# STM32-E407_Rev_E.net
KiCad netlist of a schematic drawn in EAGLE
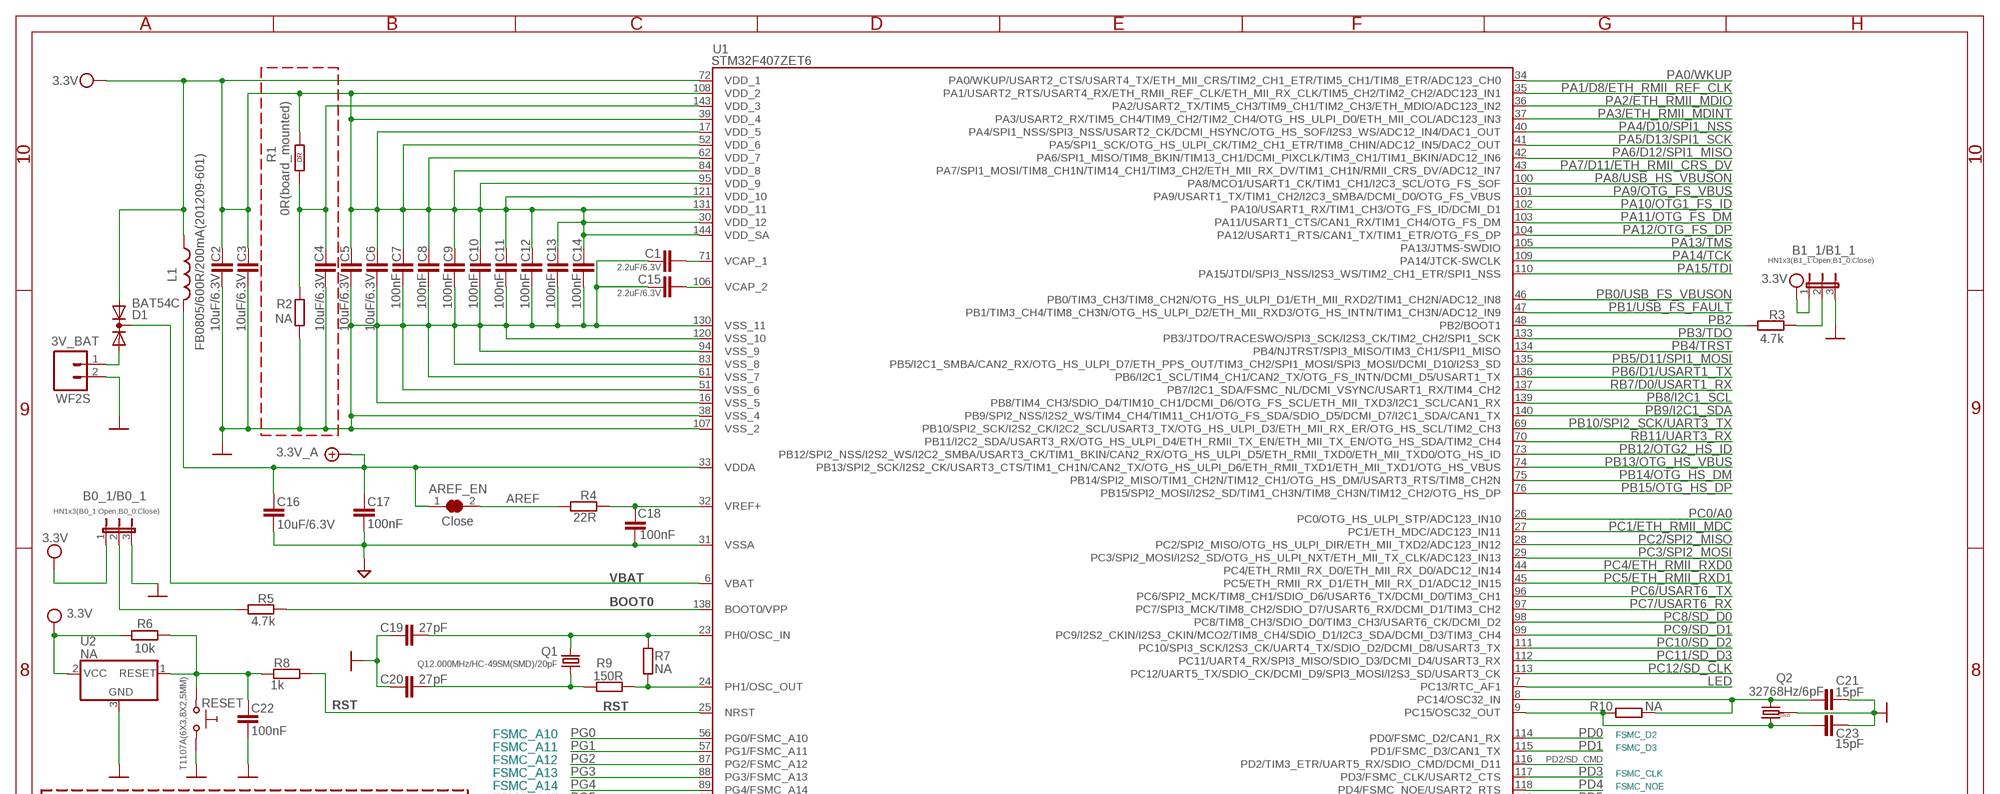
[diagram p0: schematic, sheet 1, part 1 of 2]
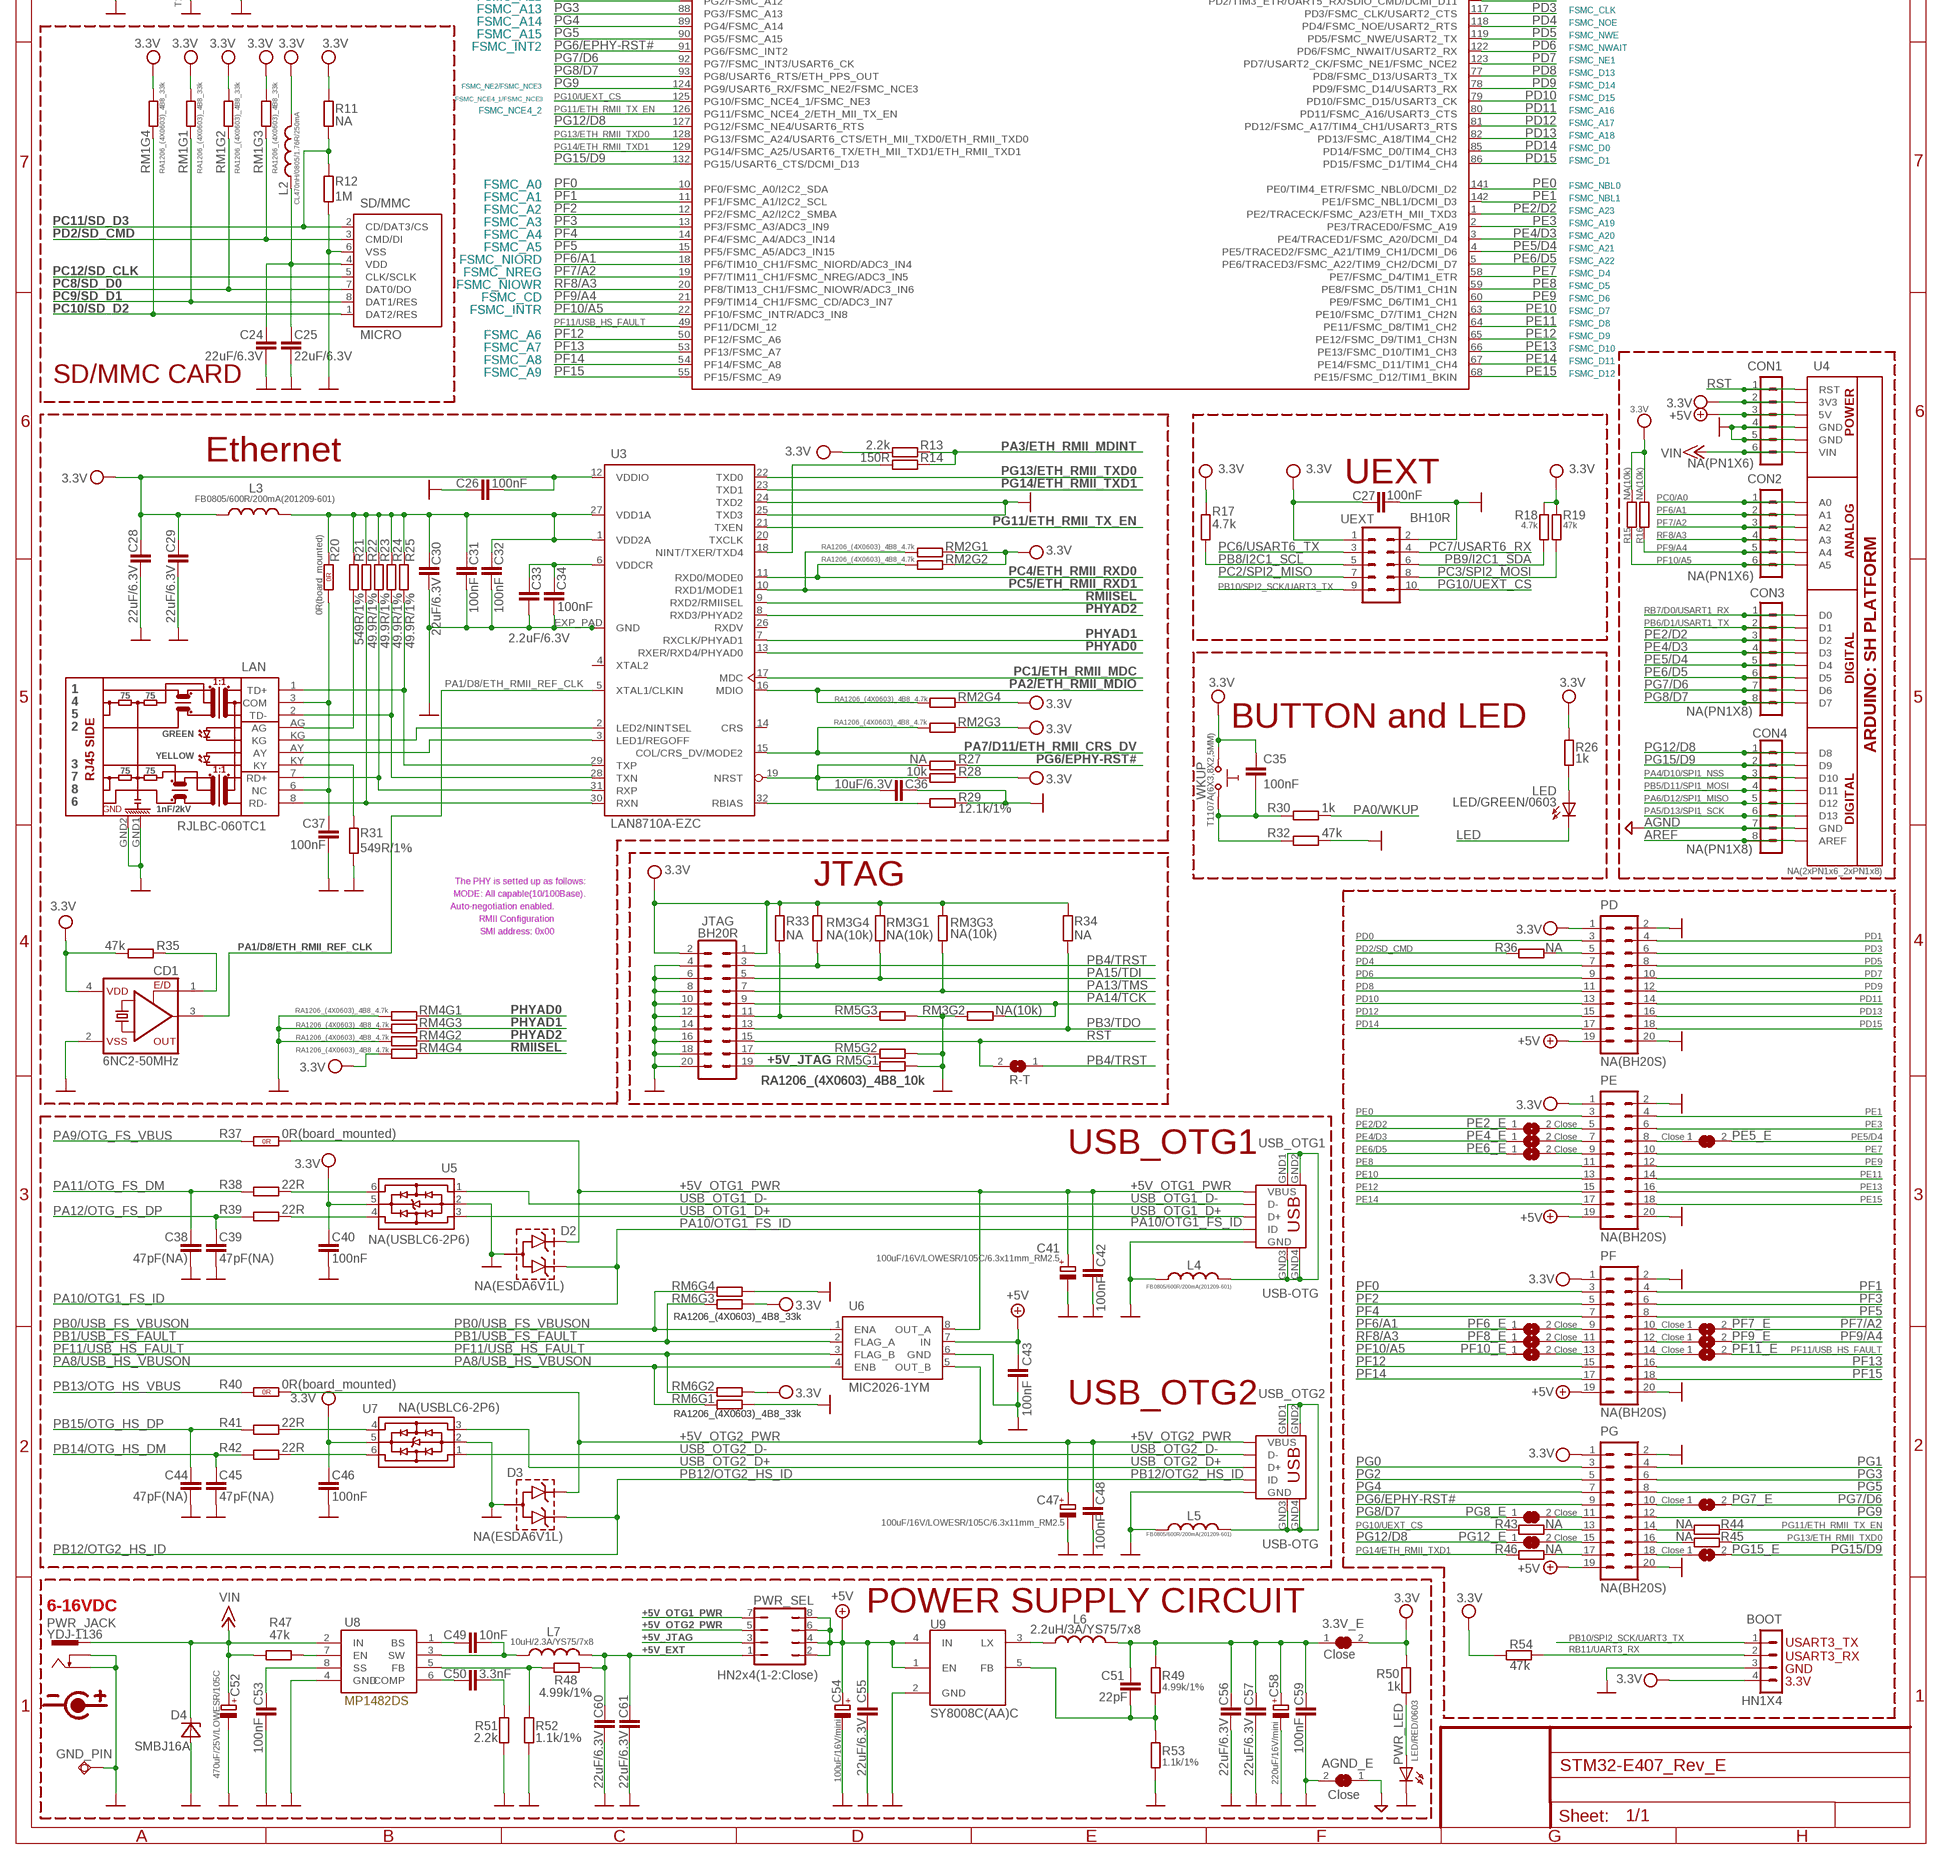
[diagram p1: schematic, sheet 1, part 2 of 2]

(export (version "E")
  (design (tool "Eeschema 10.0.6"))
  (components
    (comp (ref "3.3V_E")
      (value "Close")
      (footprint "eagle-import:SJ_1_SMALLER_CLOSE")
      (libsource (lib "eagle-import") (part "SJSJ_1_SMALLER_CLOSE"))
    )
    (comp (ref "3V_BAT")
      (value "WF2S")
      (footprint "eagle-import:CON2.54MM-2-0")
      (libsource (lib "eagle-import") (part "CON2PV2-2.54MM"))
    )
    (comp (ref "AGND_E")
      (value "Close")
      (footprint "eagle-import:SJ_1_SMALLER_CLOSE")
      (libsource (lib "eagle-import") (part "SJSJ_1_SMALLER_CLOSE"))
    )
    (comp (ref "AREF_EN")
      (value "Close")
      (footprint "eagle-import:SJ_1_SMALLER_CLOSE")
      (libsource (lib "eagle-import") (part "SJSJ_1_SMALLER_CLOSE"))
    )
    (comp (ref "B0_1/B0_1")
      (value "HN1x3(B0_1:Open;B0_0:Close)")
      (footprint "eagle-import:JP2")
      (libsource (lib "eagle-import") (part "JP2E"))
    )
    (comp (ref "B1_1/B1_1")
      (value "HN1x3(B1_1:Open;B1_0:Close)")
      (footprint "eagle-import:JP2")
      (libsource (lib "eagle-import") (part "JP2E"))
    )
    (comp (ref "BOOT")
      (value "HN1X4")
      (footprint "eagle-import:HN1X4")
      (libsource (lib "eagle-import") (part "CON4HN1X4"))
    )
    (comp (ref "C1")
      (value "2.2uF/6.3V")
      (footprint "eagle-import:C0603_DWS")
      (libsource (lib "eagle-import") (part "C-EUC0603_DWS"))
    )
    (comp (ref "C2")
      (value "10uF/6.3V")
      (footprint "eagle-import:C0603_DWS")
      (libsource (lib "eagle-import") (part "C-EUC0603_DWS"))
    )
    (comp (ref "C3")
      (value "10uF/6.3V")
      (footprint "eagle-import:C0603_DWS")
      (libsource (lib "eagle-import") (part "C-EUC0603_DWS"))
    )
    (comp (ref "C4")
      (value "10uF/6.3V")
      (footprint "eagle-import:C0603_DWS")
      (libsource (lib "eagle-import") (part "C-EUC0603_DWS"))
    )
    (comp (ref "C5")
      (value "10uF/6.3V")
      (footprint "eagle-import:C0603_DWS")
      (libsource (lib "eagle-import") (part "C-EUC0603_DWS"))
    )
    (comp (ref "C6")
      (value "10uF/6.3V")
      (footprint "eagle-import:C0603_DWS")
      (libsource (lib "eagle-import") (part "C-EUC0603_DWS"))
    )
    (comp (ref "C7")
      (value "100nF")
      (footprint "eagle-import:C0603_DWS")
      (libsource (lib "eagle-import") (part "C-EUC0603_DWS"))
    )
    (comp (ref "C8")
      (value "100nF")
      (footprint "eagle-import:C0603_DWS")
      (libsource (lib "eagle-import") (part "C-EUC0603_DWS"))
    )
    (comp (ref "C9")
      (value "100nF")
      (footprint "eagle-import:C0603_DWS")
      (libsource (lib "eagle-import") (part "C-EUC0603_DWS"))
    )
    (comp (ref "C10")
      (value "100nF")
      (footprint "eagle-import:C0603_DWS")
      (libsource (lib "eagle-import") (part "C-EUC0603_DWS"))
    )
    (comp (ref "C11")
      (value "100nF")
      (footprint "eagle-import:C0603_DWS")
      (libsource (lib "eagle-import") (part "C-EUC0603_DWS"))
    )
    (comp (ref "C12")
      (value "100nF")
      (footprint "eagle-import:C0603_DWS")
      (libsource (lib "eagle-import") (part "C-EUC0603_DWS"))
    )
    (comp (ref "C13")
      (value "100nF")
      (footprint "eagle-import:C0603_DWS")
      (libsource (lib "eagle-import") (part "C-EUC0603_DWS"))
    )
    (comp (ref "C14")
      (value "100nF")
      (footprint "eagle-import:C0603_DWS")
      (libsource (lib "eagle-import") (part "C-EUC0603_DWS"))
    )
    (comp (ref "C15")
      (value "2.2uF/6.3V")
      (footprint "eagle-import:C0603_DWS")
      (libsource (lib "eagle-import") (part "C-EUC0603_DWS"))
    )
    (comp (ref "C16")
      (value "10uF/6.3V")
      (footprint "eagle-import:C0603_DWS")
      (libsource (lib "eagle-import") (part "C-EUC0603_DWS"))
    )
    (comp (ref "C17")
      (value "100nF")
      (footprint "eagle-import:C0603_DWS")
      (libsource (lib "eagle-import") (part "C-EUC0603_DWS"))
    )
    (comp (ref "C18")
      (value "100nF")
      (footprint "eagle-import:C0603_DWS")
      (libsource (lib "eagle-import") (part "C-EUC0603_DWS"))
    )
    (comp (ref "C19")
      (value "27pF")
      (footprint "eagle-import:C0603_DWS")
      (libsource (lib "eagle-import") (part "C-EUC0603_DWS"))
    )
    (comp (ref "C20")
      (value "27pF")
      (footprint "eagle-import:C0603_DWS")
      (libsource (lib "eagle-import") (part "C-EUC0603_DWS"))
    )
    (comp (ref "C21")
      (value "15pF")
      (footprint "eagle-import:C0603_DWS")
      (libsource (lib "eagle-import") (part "C-EUC0603_DWS"))
    )
    (comp (ref "C22")
      (value "100nF")
      (footprint "eagle-import:C0603_DWS")
      (libsource (lib "eagle-import") (part "C-EUC0603_DWS"))
    )
    (comp (ref "C23")
      (value "15pF")
      (footprint "eagle-import:C0603_DWS")
      (libsource (lib "eagle-import") (part "C-EUC0603_DWS"))
    )
    (comp (ref "C24")
      (value "22uF/6.3V")
      (footprint "eagle-import:C0603_DWS")
      (libsource (lib "eagle-import") (part "C-EUC0603_DWS"))
    )
    (comp (ref "C25")
      (value "22uF/6.3V")
      (footprint "eagle-import:C0603_DWS")
      (libsource (lib "eagle-import") (part "C-EUC0603_DWS"))
    )
    (comp (ref "C26")
      (value "100nF")
      (footprint "eagle-import:C0603_DWS")
      (libsource (lib "eagle-import") (part "C-EUC0603_DWS"))
    )
    (comp (ref "C27")
      (value "100nF")
      (footprint "eagle-import:C0603_DWS")
      (libsource (lib "eagle-import") (part "C-EUC0603_DWS"))
    )
    (comp (ref "C28")
      (value "22uF/6.3V")
      (footprint "eagle-import:C0603_DWS")
      (libsource (lib "eagle-import") (part "C-EUC0603_DWS"))
    )
    (comp (ref "C29")
      (value "22uF/6.3V")
      (footprint "eagle-import:C0603_DWS")
      (libsource (lib "eagle-import") (part "C-EUC0603_DWS"))
    )
    (comp (ref "C30")
      (value "22uF/6.3V")
      (footprint "eagle-import:C0603_DWS")
      (libsource (lib "eagle-import") (part "C-EUC0603_DWS"))
    )
    (comp (ref "C31")
      (value "100nF")
      (footprint "eagle-import:C0603_DWS")
      (libsource (lib "eagle-import") (part "C-EUC0603_DWS"))
    )
    (comp (ref "C32")
      (value "100nF")
      (footprint "eagle-import:C0603_DWS")
      (libsource (lib "eagle-import") (part "C-EUC0603_DWS"))
    )
    (comp (ref "C33")
      (value "2.2uF/6.3V")
      (footprint "eagle-import:C0603_DWS")
      (libsource (lib "eagle-import") (part "C-EUC0603_DWS"))
    )
    (comp (ref "C34")
      (value "100nF")
      (footprint "eagle-import:C0603_DWS")
      (libsource (lib "eagle-import") (part "C-EUC0603_DWS"))
    )
    (comp (ref "C35")
      (value "100nF")
      (footprint "eagle-import:C0603_DWS")
      (libsource (lib "eagle-import") (part "C-EUC0603_DWS"))
    )
    (comp (ref "C36")
      (value "10uF/6.3V")
      (footprint "eagle-import:C0603_DWS")
      (libsource (lib "eagle-import") (part "C-EUC0603_DWS"))
    )
    (comp (ref "C37")
      (value "100nF")
      (footprint "eagle-import:C0603_DWS")
      (libsource (lib "eagle-import") (part "C-EUC0603_DWS"))
    )
    (comp (ref "C38")
      (value "47pF(NA)")
      (footprint "eagle-import:C0603_DWS")
      (libsource (lib "eagle-import") (part "C-EUC0603_DWS"))
    )
    (comp (ref "C39")
      (value "47pF(NA)")
      (footprint "eagle-import:C0603_DWS")
      (libsource (lib "eagle-import") (part "C-EUC0603_DWS"))
    )
    (comp (ref "C40")
      (value "100nF")
      (footprint "eagle-import:C0603_DWS")
      (libsource (lib "eagle-import") (part "C-EUC0603_DWS"))
    )
    (comp (ref "C41")
      (value "100uF/16V/LOWESR/105C/6.3x11mm_RM2.5")
      (footprint "eagle-import:E2,5-6,3")
      (libsource (lib "eagle-import") (part "CPOL-EUE2.5-6.3"))
    )
    (comp (ref "C42")
      (value "100nF")
      (footprint "eagle-import:C0603_DWS")
      (libsource (lib "eagle-import") (part "C-EUC0603_DWS"))
    )
    (comp (ref "C43")
      (value "100nF")
      (footprint "eagle-import:C0603_DWS")
      (libsource (lib "eagle-import") (part "C-EUC0603_DWS"))
    )
    (comp (ref "C44")
      (value "47pF(NA)")
      (footprint "eagle-import:C0603_DWS")
      (libsource (lib "eagle-import") (part "C-EUC0603_DWS"))
    )
    (comp (ref "C45")
      (value "47pF(NA)")
      (footprint "eagle-import:C0603_DWS")
      (libsource (lib "eagle-import") (part "C-EUC0603_DWS"))
    )
    (comp (ref "C46")
      (value "100nF")
      (footprint "eagle-import:C0603_DWS")
      (libsource (lib "eagle-import") (part "C-EUC0603_DWS"))
    )
    (comp (ref "C47")
      (value "100uF/16V/LOWESR/105C/6.3x11mm_RM2.5")
      (footprint "eagle-import:E2,5-6,3")
      (libsource (lib "eagle-import") (part "CPOL-EUE2.5-6.3"))
    )
    (comp (ref "C48")
      (value "100nF")
      (footprint "eagle-import:C0603_DWS")
      (libsource (lib "eagle-import") (part "C-EUC0603_DWS"))
    )
    (comp (ref "C49")
      (value "10nF")
      (footprint "eagle-import:C0603_DWS")
      (libsource (lib "eagle-import") (part "C-EUC0603_DWS"))
    )
    (comp (ref "C50")
      (value "3.3nF")
      (footprint "eagle-import:C0603_DWS")
      (libsource (lib "eagle-import") (part "C-EUC0603_DWS"))
    )
    (comp (ref "C51")
      (value "22pF")
      (footprint "eagle-import:C0603_DWS")
      (libsource (lib "eagle-import") (part "C-EUC0603_DWS"))
    )
    (comp (ref "C52")
      (value "470uF/25V/LOWESR/105C")
      (footprint "eagle-import:E5-10,5")
      (libsource (lib "eagle-import") (part "CPOL-EUE5-10.5"))
    )
    (comp (ref "C53")
      (value "100nF")
      (footprint "eagle-import:C0603_DWS")
      (libsource (lib "eagle-import") (part "C-EUC0603_DWS"))
    )
    (comp (ref "C54")
      (value "100uF/16V/mini")
      (footprint "eagle-import:E2,5-6")
      (libsource (lib "eagle-import") (part "CPOL-EUE2.5-6"))
    )
    (comp (ref "C55")
      (value "22uF/6.3V")
      (footprint "eagle-import:C0603_DWS")
      (libsource (lib "eagle-import") (part "C-EUC0603_DWS"))
    )
    (comp (ref "C56")
      (value "22uF/6.3V")
      (footprint "eagle-import:C0603_DWS")
      (libsource (lib "eagle-import") (part "C-EUC0603_DWS"))
    )
    (comp (ref "C57")
      (value "22uF/6.3V")
      (footprint "eagle-import:C0603_DWS")
      (libsource (lib "eagle-import") (part "C-EUC0603_DWS"))
    )
    (comp (ref "C58")
      (value "220uF/16V/mini")
      (footprint "eagle-import:E3,5-8")
      (libsource (lib "eagle-import") (part "CPOL-EUE3.5-8"))
    )
    (comp (ref "C59")
      (value "100nF")
      (footprint "eagle-import:C0603_DWS")
      (libsource (lib "eagle-import") (part "C-EUC0603_DWS"))
    )
    (comp (ref "C60")
      (value "22uF/6.3V")
      (footprint "eagle-import:C0603_DWS")
      (libsource (lib "eagle-import") (part "C-EUC0603_DWS"))
    )
    (comp (ref "C61")
      (value "22uF/6.3V")
      (footprint "eagle-import:C0603_DWS")
      (libsource (lib "eagle-import") (part "C-EUC0603_DWS"))
    )
    (comp (ref "CD1")
      (value "6NC2-50MHz")
      (footprint "eagle-import:7X5MM_CLOCK_DRIVER")
      (libsource (lib "eagle-import") (part "6NC2_CLOCK_DRIVER"))
    )
    (comp (ref "CON1")
      (value "NA(PN1X6)")
      (footprint "eagle-import:PN1X6")
      (libsource (lib "eagle-import") (part "CON6PN1X6"))
    )
    (comp (ref "CON2")
      (value "NA(PN1X6)")
      (footprint "eagle-import:PN1X6")
      (libsource (lib "eagle-import") (part "CON6PN1X6"))
    )
    (comp (ref "CON3")
      (value "NA(PN1X8)")
      (footprint "eagle-import:PN1X8")
      (libsource (lib "eagle-import") (part "CON8PN1X8"))
    )
    (comp (ref "CON4")
      (value "NA(PN1X8)")
      (footprint "eagle-import:PN1X8")
      (libsource (lib "eagle-import") (part "CON8PN1X8"))
    )
    (comp (ref "D1")
      (value "BAT54C")
      (footprint "eagle-import:SOT23C")
      (libsource (lib "eagle-import") (part "DIODE_AC-CA_"))
    )
    (comp (ref "D2")
      (value "NA(ESDA6V1L)")
      (footprint "eagle-import:SOT-23")
      (libsource (lib "eagle-import") (part "MMBZ5V6ALT1"))
    )
    (comp (ref "D3")
      (value "NA(ESDA6V1L)")
      (footprint "eagle-import:SOT-23")
      (libsource (lib "eagle-import") (part "MMBZ5V6ALT1"))
    )
    (comp (ref "D4")
      (value "SMBJ16A")
      (footprint "eagle-import:DO214AA")
      (libsource (lib "eagle-import") (part "SMBJ16A"))
    )
    (comp (ref "GND_PIN")
      (value "TESTPAD3")
      (footprint "eagle-import:TEST_PAD40_70_SQUARE")
      (libsource (lib "eagle-import") (part "TESTPAD3"))
    )
    (comp (ref "JTAG")
      (value "BH20R")
      (footprint "eagle-import:BH20R")
      (libsource (lib "eagle-import") (part "ML20R"))
    )
    (comp (ref "L1")
      (value "FB0805/600R/200mA(201209-601)")
      (footprint "eagle-import:L0805_5MIL_DWS")
      (libsource (lib "eagle-import") (part "L-USL0805_5MIL_DWS"))
    )
    (comp (ref "L2")
      (value "CL470nH/0805/1.76R/250mA")
      (footprint "eagle-import:L0805_5MIL_DWS")
      (libsource (lib "eagle-import") (part "L-USL0805_5MIL_DWS"))
    )
    (comp (ref "L3")
      (value "FB0805/600R/200mA(201209-601)")
      (footprint "eagle-import:L0805_5MIL_DWS")
      (libsource (lib "eagle-import") (part "L-USL0805_5MIL_DWS"))
    )
    (comp (ref "L4")
      (value "FB0805/600R/200mA(201209-601)")
      (footprint "eagle-import:L0805_5MIL_DWS")
      (libsource (lib "eagle-import") (part "L-USL0805_5MIL_DWS"))
    )
    (comp (ref "L5")
      (value "FB0805/600R/200mA(201209-601)")
      (footprint "eagle-import:L0805_5MIL_DWS")
      (libsource (lib "eagle-import") (part "L-USL0805_5MIL_DWS"))
    )
    (comp (ref "L6")
      (value "2.2uH/3A/YS75/7x8")
      (footprint "eagle-import:L7078")
      (libsource (lib "eagle-import") (part "L-USL7078"))
    )
    (comp (ref "L7")
      (value "10uH/2.3A/YS75/7x8")
      (footprint "eagle-import:L7078")
      (libsource (lib "eagle-import") (part "L-USL7078"))
    )
    (comp (ref "LAN")
      (value "RJLBC-060TC1")
      (footprint "eagle-import:RJLBC-060TC1")
      (libsource (lib "eagle-import") (part "RJLBC-060TC1_GND"))
    )
    (comp (ref "LED")
      (value "LED/GREEN/0603")
      (footprint "eagle-import:LED-0603")
      (libsource (lib "eagle-import") (part "LED0603DWS"))
    )
    (comp (ref "PD")
      (value "NA(BH20S)")
      (footprint "eagle-import:ML20-MALE")
      (libsource (lib "eagle-import") (part "ML20"))
    )
    (comp (ref "PE")
      (value "NA(BH20S)")
      (footprint "eagle-import:ML20-MALE")
      (libsource (lib "eagle-import") (part "ML20"))
    )
    (comp (ref "PE2_E")
      (value "Close")
      (footprint "eagle-import:SJ_1_SMALLER_CLOSE")
      (libsource (lib "eagle-import") (part "SJSJ_1_SMALLER_CLOSE"))
    )
    (comp (ref "PE4_E")
      (value "Close")
      (footprint "eagle-import:SJ_1_SMALLER_CLOSE")
      (libsource (lib "eagle-import") (part "SJSJ_1_SMALLER_CLOSE"))
    )
    (comp (ref "PE5_E")
      (value "Close")
      (footprint "eagle-import:SJ_1_SMALLER_CLOSE")
      (libsource (lib "eagle-import") (part "SJSJ_1_SMALLER_CLOSE"))
    )
    (comp (ref "PE6_E")
      (value "Close")
      (footprint "eagle-import:SJ_1_SMALLER_CLOSE")
      (libsource (lib "eagle-import") (part "SJSJ_1_SMALLER_CLOSE"))
    )
    (comp (ref "PF")
      (value "NA(BH20S)")
      (footprint "eagle-import:ML20-MALE")
      (libsource (lib "eagle-import") (part "ML20"))
    )
    (comp (ref "PF6_E")
      (value "Close")
      (footprint "eagle-import:SJ_1_SMALLER_CLOSE")
      (libsource (lib "eagle-import") (part "SJSJ_1_SMALLER_CLOSE"))
    )
    (comp (ref "PF7_E")
      (value "Close")
      (footprint "eagle-import:SJ_1_SMALLER_CLOSE")
      (libsource (lib "eagle-import") (part "SJSJ_1_SMALLER_CLOSE"))
    )
    (comp (ref "PF8_E")
      (value "Close")
      (footprint "eagle-import:SJ_1_SMALLER_CLOSE")
      (libsource (lib "eagle-import") (part "SJSJ_1_SMALLER_CLOSE"))
    )
    (comp (ref "PF9_E")
      (value "Close")
      (footprint "eagle-import:SJ_1_SMALLER_CLOSE")
      (libsource (lib "eagle-import") (part "SJSJ_1_SMALLER_CLOSE"))
    )
    (comp (ref "PF10_E")
      (value "Close")
      (footprint "eagle-import:SJ_1_SMALLER_CLOSE")
      (libsource (lib "eagle-import") (part "SJSJ_1_SMALLER_CLOSE"))
    )
    (comp (ref "PF11_E")
      (value "Close")
      (footprint "eagle-import:SJ_1_SMALLER_CLOSE")
      (libsource (lib "eagle-import") (part "SJSJ_1_SMALLER_CLOSE"))
    )
    (comp (ref "PG")
      (value "NA(BH20S)")
      (footprint "eagle-import:ML20-MALE")
      (libsource (lib "eagle-import") (part "ML20"))
    )
    (comp (ref "PG7_E")
      (value "Close")
      (footprint "eagle-import:SJ_1_SMALLER_CLOSE")
      (libsource (lib "eagle-import") (part "SJSJ_1_SMALLER_CLOSE"))
    )
    (comp (ref "PG8_E")
      (value "Close")
      (footprint "eagle-import:SJ_1_SMALLER_CLOSE")
      (libsource (lib "eagle-import") (part "SJSJ_1_SMALLER_CLOSE"))
    )
    (comp (ref "PG12_E")
      (value "Close")
      (footprint "eagle-import:SJ_1_SMALLER_CLOSE")
      (libsource (lib "eagle-import") (part "SJSJ_1_SMALLER_CLOSE"))
    )
    (comp (ref "PG15_E")
      (value "Close")
      (footprint "eagle-import:SJ_1_SMALLER_CLOSE")
      (libsource (lib "eagle-import") (part "SJSJ_1_SMALLER_CLOSE"))
    )
    (comp (ref "PWR_JACK")
      (value "YDJ-1136")
      (footprint "eagle-import:PWR_JACK_UNI_MILLING")
      (libsource (lib "eagle-import") (part "PWR-JAKPWR_JACK_UNI_MILLING"))
    )
    (comp (ref "PWR_LED")
      (value "LED/RED/0603")
      (footprint "eagle-import:LED-0603")
      (libsource (lib "eagle-import") (part "LED0603DWS"))
    )
    (comp (ref "PWR_SEL")
      (value "HN2x4(1-2:Close)")
      (footprint "eagle-import:JP4Q_2")
      (libsource (lib "eagle-import") (part "JP4QNEW"))
    )
    (comp (ref "Q1")
      (value "Q12.000MHz/HC-49SM(SMD)/20pF")
      (footprint "eagle-import:HC49_SMD2_THIN")
      (libsource (lib "eagle-import") (part "HC49/S1"))
    )
    (comp (ref "Q2")
      (value "32768Hz/6pF")
      (footprint "eagle-import:TC26H_3_REPAIR_SMD")
      (libsource (lib "eagle-import") (part "Q_GND1"))
    )
    (comp (ref "R-T")
      (value "Open")
      (footprint "eagle-import:SJ_1_SMALLER")
      (libsource (lib "eagle-import") (part "SJSJ_SMALLER"))
    )
    (comp (ref "R1")
      (value "0R(board_mounted)")
      (footprint "eagle-import:0603_0R")
      (libsource (lib "eagle-import") (part "R_0R0R(NA)"))
    )
    (comp (ref "R2")
      (value "NA")
      (footprint "eagle-import:R0603_5MIL_DWS")
      (libsource (lib "eagle-import") (part "R-EU_R0603_5MIL_DWS"))
    )
    (comp (ref "R3")
      (value "4.7k")
      (footprint "eagle-import:R0603_5MIL_DWS")
      (libsource (lib "eagle-import") (part "R-EU_R0603_5MIL_DWS"))
    )
    (comp (ref "R4")
      (value "22R")
      (footprint "eagle-import:R0603_5MIL_DWS")
      (libsource (lib "eagle-import") (part "R-EU_R0603_5MIL_DWS"))
    )
    (comp (ref "R5")
      (value "4.7k")
      (footprint "eagle-import:R0603_5MIL_DWS")
      (libsource (lib "eagle-import") (part "R-EU_R0603_5MIL_DWS"))
    )
    (comp (ref "R6")
      (value "10k")
      (footprint "eagle-import:R0603_5MIL_DWS")
      (libsource (lib "eagle-import") (part "R-EU_R0603_5MIL_DWS"))
    )
    (comp (ref "R7")
      (value "NA")
      (footprint "eagle-import:R0603_5MIL_DWS")
      (libsource (lib "eagle-import") (part "R-EU_R0603_5MIL_DWS"))
    )
    (comp (ref "R8")
      (value "1k")
      (footprint "eagle-import:R0603_5MIL_DWS")
      (libsource (lib "eagle-import") (part "R-EU_R0603_5MIL_DWS"))
    )
    (comp (ref "R9")
      (value "150R")
      (footprint "eagle-import:R0603_5MIL_DWS")
      (libsource (lib "eagle-import") (part "R-EU_R0603_5MIL_DWS"))
    )
    (comp (ref "R10")
      (value "NA")
      (footprint "eagle-import:R0603_5MIL_DWS")
      (libsource (lib "eagle-import") (part "R-EU_R0603_5MIL_DWS"))
    )
    (comp (ref "R11")
      (value "NA")
      (footprint "eagle-import:R0603_5MIL_DWS")
      (libsource (lib "eagle-import") (part "R-EU_R0603_5MIL_DWS"))
    )
    (comp (ref "R12")
      (value "1M")
      (footprint "eagle-import:R0603_5MIL_DWS")
      (libsource (lib "eagle-import") (part "R-EU_R0603_5MIL_DWS"))
    )
    (comp (ref "R13")
      (value "2.2k")
      (footprint "eagle-import:R0603_5MIL_DWS")
      (libsource (lib "eagle-import") (part "R-EU_R0603_5MIL_DWS"))
    )
    (comp (ref "R14")
      (value "150R")
      (footprint "eagle-import:R0603_5MIL_DWS")
      (libsource (lib "eagle-import") (part "R-EU_R0603_5MIL_DWS"))
    )
    (comp (ref "R15")
      (value "NA(10k)")
      (footprint "eagle-import:R0603_5MIL_DWS")
      (libsource (lib "eagle-import") (part "R-EU_R0603_5MIL_DWS"))
    )
    (comp (ref "R16")
      (value "NA(10k)")
      (footprint "eagle-import:R0603_5MIL_DWS")
      (libsource (lib "eagle-import") (part "R-EU_R0603_5MIL_DWS"))
    )
    (comp (ref "R17")
      (value "4.7k")
      (footprint "eagle-import:R0603_5MIL_DWS")
      (libsource (lib "eagle-import") (part "R-EU_R0603_5MIL_DWS"))
    )
    (comp (ref "R18")
      (value "4.7k")
      (footprint "eagle-import:R0603_5MIL_DWS")
      (libsource (lib "eagle-import") (part "R-EU_R0603_5MIL_DWS"))
    )
    (comp (ref "R19")
      (value "47k")
      (footprint "eagle-import:R0603_5MIL_DWS")
      (libsource (lib "eagle-import") (part "R-EU_R0603_5MIL_DWS"))
    )
    (comp (ref "R20")
      (value "0R(board_mounted)")
      (footprint "eagle-import:0603_0R")
      (libsource (lib "eagle-import") (part "R_0R0R(NA)"))
    )
    (comp (ref "R21")
      (value "549R/1%")
      (footprint "eagle-import:R0603_5MIL_DWS")
      (libsource (lib "eagle-import") (part "R-EU_R0603_5MIL_DWS"))
    )
    (comp (ref "R22")
      (value "49.9R/1%")
      (footprint "eagle-import:R0603_5MIL_DWS")
      (libsource (lib "eagle-import") (part "R-EU_R0603_5MIL_DWS"))
    )
    (comp (ref "R23")
      (value "49.9R/1%")
      (footprint "eagle-import:R0603_5MIL_DWS")
      (libsource (lib "eagle-import") (part "R-EU_R0603_5MIL_DWS"))
    )
    (comp (ref "R24")
      (value "49.9R/1%")
      (footprint "eagle-import:R0603_5MIL_DWS")
      (libsource (lib "eagle-import") (part "R-EU_R0603_5MIL_DWS"))
    )
    (comp (ref "R25")
      (value "49.9R/1%")
      (footprint "eagle-import:R0603_5MIL_DWS")
      (libsource (lib "eagle-import") (part "R-EU_R0603_5MIL_DWS"))
    )
    (comp (ref "R26")
      (value "1k")
      (footprint "eagle-import:R0603_5MIL_DWS")
      (libsource (lib "eagle-import") (part "R-EU_R0603_5MIL_DWS"))
    )
    (comp (ref "R27")
      (value "NA")
      (footprint "eagle-import:R0603_5MIL_DWS")
      (libsource (lib "eagle-import") (part "R-EU_R0603_5MIL_DWS"))
    )
    (comp (ref "R28")
      (value "10k")
      (footprint "eagle-import:R0603_5MIL_DWS")
      (libsource (lib "eagle-import") (part "R-EU_R0603_5MIL_DWS"))
    )
    (comp (ref "R29")
      (value "12.1k/1%")
      (footprint "eagle-import:R0603_5MIL_DWS")
      (libsource (lib "eagle-import") (part "R-EU_R0603_5MIL_DWS"))
    )
    (comp (ref "R30")
      (value "1k")
      (footprint "eagle-import:R0603_5MIL_DWS")
      (libsource (lib "eagle-import") (part "R-EU_R0603_5MIL_DWS"))
    )
    (comp (ref "R31")
      (value "549R/1%")
      (footprint "eagle-import:R0603_5MIL_DWS")
      (libsource (lib "eagle-import") (part "R-EU_R0603_5MIL_DWS"))
    )
    (comp (ref "R32")
      (value "47k")
      (footprint "eagle-import:R0603_5MIL_DWS")
      (libsource (lib "eagle-import") (part "R-EU_R0603_5MIL_DWS"))
    )
    (comp (ref "R33")
      (value "NA")
      (footprint "eagle-import:R0603_5MIL_DWS")
      (libsource (lib "eagle-import") (part "R-EU_R0603_5MIL_DWS"))
    )
    (comp (ref "R34")
      (value "NA")
      (footprint "eagle-import:R0603_5MIL_DWS")
      (libsource (lib "eagle-import") (part "R-EU_R0603_5MIL_DWS"))
    )
    (comp (ref "R35")
      (value "47k")
      (footprint "eagle-import:R0603_5MIL_DWS")
      (libsource (lib "eagle-import") (part "R-EU_R0603_5MIL_DWS"))
    )
    (comp (ref "R36")
      (value "NA")
      (footprint "eagle-import:R0603_5MIL_DWS")
      (libsource (lib "eagle-import") (part "R-EU_R0603_5MIL_DWS"))
    )
    (comp (ref "R37")
      (value "0R(board_mounted)")
      (footprint "eagle-import:0603_0R")
      (libsource (lib "eagle-import") (part "R_0R0R(NA)"))
    )
    (comp (ref "R38")
      (value "22R")
      (footprint "eagle-import:R0603_5MIL_DWS")
      (libsource (lib "eagle-import") (part "R-EU_R0603_5MIL_DWS"))
    )
    (comp (ref "R39")
      (value "22R")
      (footprint "eagle-import:R0603_5MIL_DWS")
      (libsource (lib "eagle-import") (part "R-EU_R0603_5MIL_DWS"))
    )
    (comp (ref "R40")
      (value "0R(board_mounted)")
      (footprint "eagle-import:0603_0R")
      (libsource (lib "eagle-import") (part "R_0R0R(NA)"))
    )
    (comp (ref "R41")
      (value "22R")
      (footprint "eagle-import:R0603_5MIL_DWS")
      (libsource (lib "eagle-import") (part "R-EU_R0603_5MIL_DWS"))
    )
    (comp (ref "R42")
      (value "22R")
      (footprint "eagle-import:R0603_5MIL_DWS")
      (libsource (lib "eagle-import") (part "R-EU_R0603_5MIL_DWS"))
    )
    (comp (ref "R43")
      (value "NA")
      (footprint "eagle-import:R0603_5MIL_DWS")
      (libsource (lib "eagle-import") (part "R-EU_R0603_5MIL_DWS"))
    )
    (comp (ref "R44")
      (value "NA")
      (footprint "eagle-import:R0603_5MIL_DWS")
      (libsource (lib "eagle-import") (part "R-EU_R0603_5MIL_DWS"))
    )
    (comp (ref "R45")
      (value "NA")
      (footprint "eagle-import:R0603_5MIL_DWS")
      (libsource (lib "eagle-import") (part "R-EU_R0603_5MIL_DWS"))
    )
    (comp (ref "R46")
      (value "NA")
      (footprint "eagle-import:R0603_5MIL_DWS")
      (libsource (lib "eagle-import") (part "R-EU_R0603_5MIL_DWS"))
    )
    (comp (ref "R47")
      (value "47k")
      (footprint "eagle-import:R0603_5MIL_DWS")
      (libsource (lib "eagle-import") (part "R-EU_R0603_5MIL_DWS"))
    )
    (comp (ref "R48")
      (value "4.99k/1%")
      (footprint "eagle-import:R0603_5MIL_DWS")
      (libsource (lib "eagle-import") (part "R-EU_R0603_5MIL_DWS"))
    )
    (comp (ref "R49")
      (value "4.99k/1%")
      (footprint "eagle-import:R0603_5MIL_DWS")
      (libsource (lib "eagle-import") (part "R-EU_R0603_5MIL_DWS"))
    )
    (comp (ref "R50")
      (value "1k")
      (footprint "eagle-import:R0603_5MIL_DWS")
      (libsource (lib "eagle-import") (part "R-EU_R0603_5MIL_DWS"))
    )
    (comp (ref "R51")
      (value "2.2k")
      (footprint "eagle-import:R0603_5MIL_DWS")
      (libsource (lib "eagle-import") (part "R-EU_R0603_5MIL_DWS"))
    )
    (comp (ref "R52")
      (value "1.1k/1%")
      (footprint "eagle-import:R0603_5MIL_DWS")
      (libsource (lib "eagle-import") (part "R-EU_R0603_5MIL_DWS"))
    )
    (comp (ref "R53")
      (value "1.1k/1%")
      (footprint "eagle-import:R0603_5MIL_DWS")
      (libsource (lib "eagle-import") (part "R-EU_R0603_5MIL_DWS"))
    )
    (comp (ref "R54")
      (value "47k")
      (footprint "eagle-import:R0603_5MIL_DWS")
      (libsource (lib "eagle-import") (part "R-EU_R0603_5MIL_DWS"))
    )
    (comp (ref "RESET")
      (value "T1107A(6X3,8X2,5MM)")
      (footprint "eagle-import:WS-TAKT_6X3.5_SMD_NOCREAM")
      (libsource (lib "eagle-import") (part "SW-TAKTT1107A(6X3,8X2,5MM)"))
    )
    (comp (ref "RM1")
      (value "RA1206_(4X0603)_4B8_33k")
      (footprint "eagle-import:R_MATRIX_4")
      (libsource (lib "eagle-import") (part "R_MATRIX_4E"))
    )
    (comp (ref "RM2")
      (value "RA1206_(4X0603)_4B8_4.7k")
      (footprint "eagle-import:R_MATRIX_4")
      (libsource (lib "eagle-import") (part "R_MATRIX_4E"))
    )
    (comp (ref "RM3")
      (value "NA(10k)")
      (footprint "eagle-import:R_MATRIX_4")
      (libsource (lib "eagle-import") (part "R_MATRIX_4E"))
    )
    (comp (ref "RM4")
      (value "RA1206_(4X0603)_4B8_4.7k")
      (footprint "eagle-import:R_MATRIX_4")
      (libsource (lib "eagle-import") (part "R_MATRIX_4E"))
    )
    (comp (ref "RM5")
      (value "RA1206_(4X0603)_4B8_10k")
      (footprint "eagle-import:R_MATRIX_4")
      (libsource (lib "eagle-import") (part "R_MATRIX_4E"))
    )
    (comp (ref "RM6")
      (value "RA1206_(4X0603)_4B8_33k")
      (footprint "eagle-import:R_MATRIX_4")
      (libsource (lib "eagle-import") (part "R_MATRIX_4E"))
    )
    (comp (ref "SD/MMC")
      (value "MICRO")
      (footprint "eagle-import:TFR_C-MEM-CON")
      (libsource (lib "eagle-import") (part "MICRO_SD/MMC_NEW"))
    )
    (comp (ref "U1")
      (value "STM32F407ZET6")
      (footprint "eagle-import:LQFP144")
      (libsource (lib "eagle-import") (part "STM32F207ZET6"))
    )
    (comp (ref "U2")
      (value "NA")
      (footprint "eagle-import:SOT23")
      (libsource (lib "eagle-import") (part "RESETMCP130T-300-I/TT"))
    )
    (comp (ref "U3")
      (value "LAN8710A-EZC")
      (footprint "eagle-import:QFN-32(DRILLS)")
      (libsource (lib "eagle-import") (part "LAN8710A-EZC"))
    )
    (comp (ref "U4")
      (value "NA(2xPN1x6_2xPN1x8)")
      (footprint "eagle-import:ARDUINO_SHIELD_PLATFORM_WITHOUT_DIMENSION")
      (libsource (lib "eagle-import") (part "ARDUINO_SH_PLATFORM3"))
    )
    (comp (ref "U5")
      (value "NA(USBLC6-2P6)")
      (footprint "eagle-import:USBLC6-2P6")
      (libsource (lib "eagle-import") (part "USBLC6-2"))
    )
    (comp (ref "U6")
      (value "MIC2026-1YM")
      (footprint "eagle-import:SO-8")
      (libsource (lib "eagle-import") (part "MIC2026-1YM"))
    )
    (comp (ref "U7")
      (value "NA(USBLC6-2P6)")
      (footprint "eagle-import:USBLC6-2P6")
      (libsource (lib "eagle-import") (part "USBLC6-2"))
    )
    (comp (ref "U8")
      (value "MP1482DS")
      (footprint "eagle-import:SOIC8")
      (libsource (lib "eagle-import") (part "MP1482"))
    )
    (comp (ref "U9")
      (value "SY8008C(AA)C")
      (footprint "eagle-import:SOT23-5")
      (libsource (lib "eagle-import") (part "SY8008"))
    )
    (comp (ref "UEXT")
      (value "BH10R")
      (footprint "eagle-import:BH10R")
      (libsource (lib "eagle-import") (part "ML10R"))
    )
    (comp (ref "USB_OTG1")
      (value "USB-OTG")
      (footprint "eagle-import:USB_MINI_9PIN")
      (libsource (lib "eagle-import") (part "MINI_USB9"))
    )
    (comp (ref "USB_OTG2")
      (value "USB-OTG")
      (footprint "eagle-import:USB_MINI_9PIN")
      (libsource (lib "eagle-import") (part "MINI_USB9"))
    )
    (comp (ref "WKUP")
      (value "T1107A(6X3,8X2,5MM)")
      (footprint "eagle-import:WS-TAKT_6X3.5_SMD_NOCREAM")
      (libsource (lib "eagle-import") (part "SW-TAKTT1107A(6X3,8X2,5MM)"))
    )
  )
  (nets
    (net (code "1") (name "+5V") (class "Default")
      (node (ref "C43") (pin "1") (pinfunction "1_1") (pintype "passive"))
      (node (ref "C54") (pin "+") (pinfunction "+_+") (pintype "passive"))
      (node (ref "C55") (pin "1") (pinfunction "1_1") (pintype "passive"))
      (node (ref "CON1") (pin "3") (pinfunction "3_3") (pintype "passive"))
      (node (ref "PD") (pin "19") (pinfunction "19_19") (pintype "passive"))
      (node (ref "PE") (pin "19") (pinfunction "19_19") (pintype "passive"))
      (node (ref "PF") (pin "19") (pinfunction "19_19") (pintype "passive"))
      (node (ref "PG") (pin "19") (pinfunction "19_19") (pintype "passive"))
      (node (ref "PWR_SEL") (pin "2") (pinfunction "2_2") (pintype "passive"))
      (node (ref "PWR_SEL") (pin "4") (pinfunction "4_4") (pintype "passive"))
      (node (ref "PWR_SEL") (pin "6") (pinfunction "6_6") (pintype "passive"))
      (node (ref "PWR_SEL") (pin "8") (pinfunction "8_8") (pintype "passive"))
      (node (ref "U4") (pin "5V") (pinfunction "5V_5V") (pintype "bidirectional"))
      (node (ref "U6") (pin "7") (pinfunction "IN_7") (pintype "input"))
      (node (ref "U9") (pin "1") (pinfunction "EN_1") (pintype "bidirectional"))
      (node (ref "U9") (pin "4") (pinfunction "IN_4") (pintype "bidirectional"))
    )
    (net (code "2") (name "/+5V_EXT") (class "Default")
      (node (ref "C60") (pin "1") (pinfunction "1_1") (pintype "passive"))
      (node (ref "C61") (pin "1") (pinfunction "1_1") (pintype "passive"))
      (node (ref "L7") (pin "2") (pinfunction "2_2") (pintype "passive"))
      (node (ref "PWR_SEL") (pin "1") (pinfunction "1_1") (pintype "passive"))
      (node (ref "R48") (pin "2") (pinfunction "2_2") (pintype "passive"))
    )
    (net (code "3") (name "/+5V_JTAG") (class "Default")
      (node (ref "JTAG") (pin "19") (pinfunction "19_19") (pintype "passive"))
      (node (ref "PWR_SEL") (pin "3") (pinfunction "3_3") (pintype "passive"))
      (node (ref "RM5") (pin "1.1") (pinfunction "1_1.1") (pintype "passive"))
    )
    (net (code "4") (name "/+5V_OTG1_PWR") (class "Default")
      (node (ref "C41") (pin "+") (pinfunction "+_+") (pintype "passive"))
      (node (ref "C42") (pin "1") (pinfunction "1_1") (pintype "passive"))
      (node (ref "D2") (pin "1") (pinfunction "1_1") (pintype "passive"))
      (node (ref "PWR_SEL") (pin "7") (pinfunction "7_7") (pintype "passive"))
      (node (ref "R37") (pin "2") (pinfunction "1.2_2") (pintype "passive"))
      (node (ref "U6") (pin "8") (pinfunction "OUT_A_8") (pintype "output"))
      (node (ref "USB_OTG1") (pin "VBUS") (pinfunction "VBUS_VBUS") (pintype "power_in"))
    )
    (net (code "5") (name "/+5V_OTG2_PWR") (class "Default")
      (node (ref "C47") (pin "+") (pinfunction "+_+") (pintype "passive"))
      (node (ref "C48") (pin "1") (pinfunction "1_1") (pintype "passive"))
      (node (ref "D3") (pin "1") (pinfunction "1_1") (pintype "passive"))
      (node (ref "PWR_SEL") (pin "5") (pinfunction "5_5") (pintype "passive"))
      (node (ref "R40") (pin "2") (pinfunction "1.2_2") (pintype "passive"))
      (node (ref "U6") (pin "5") (pinfunction "OUT_B_5") (pintype "output"))
      (node (ref "USB_OTG2") (pin "VBUS") (pinfunction "VBUS_VBUS") (pintype "power_in"))
    )
    (net (code "6") (name "/AREF") (class "Default")
      (node (ref "AREF_EN") (pin "2") (pinfunction "2_2") (pintype "passive"))
      (node (ref "CON4") (pin "8") (pinfunction "8_8") (pintype "passive"))
      (node (ref "R4") (pin "1") (pinfunction "1_1") (pintype "passive"))
      (node (ref "U4") (pin "AREF") (pinfunction "AREF_AREF") (pintype "bidirectional"))
    )
    (net (code "7") (name "/BOOT0") (class "Default")
      (node (ref "R5") (pin "1") (pinfunction "1_1") (pintype "passive"))
      (node (ref "U1") (pin "138") (pinfunction "BOOT0/VPP_138") (pintype "input"))
    )
    (net (code "8") (name "/LED") (class "Default")
      (node (ref "LED") (pin "C") (pinfunction "C_C") (pintype "passive"))
      (node (ref "U1") (pin "7") (pinfunction "PC13/RTC_AF1_7") (pintype "bidirectional"))
    )
    (net (code "9") (name "/PA0{slash}WKUP") (class "Default")
      (node (ref "R30") (pin "2") (pinfunction "2_2") (pintype "passive"))
      (node (ref "U1") (pin "34") (pinfunction "PA0/WKUP/USART2_CTS/USART4_TX/ETH_MII_CRS/TIM2_CH1_ETR/TIM5_CH1/TIM8_ETR/ADC123_CH0_34") (pintype "bidirectional"))
    )
    (net (code "10") (name "/PA1{slash}D8{slash}ETH_RMII_REF_CLK") (class "Default")
      (node (ref "CD1") (pin "3") (pinfunction "OUT_3") (pintype "output"))
      (node (ref "U1") (pin "35") (pinfunction "PA1/USART2_RTS/USART4_RX/ETH_RMII_REF_CLK/ETH_MII_RX_CLK/TIM5_CH2/TIM2_CH2/ADC123_IN1_35") (pintype "bidirectional"))
      (node (ref "U3") (pin "5") (pinfunction "XTAL1/CLKIN_5") (pintype "input"))
    )
    (net (code "11") (name "/PA2{slash}ETH_RMII_MDIO") (class "Default")
      (node (ref "RM2") (pin "4.2") (pinfunction "2_4.2") (pintype "passive"))
      (node (ref "U1") (pin "36") (pinfunction "PA2/USART2_TX/TIM5_CH3/TIM9_CH1/TIM2_CH3/ETH_MDIO/ADC123_IN2_36") (pintype "bidirectional"))
      (node (ref "U3") (pin "16") (pinfunction "MDIO_16") (pintype "bidirectional"))
    )
    (net (code "12") (name "/PA3{slash}ETH_RMII_MDINT") (class "Default")
      (node (ref "R13") (pin "1") (pinfunction "1_1") (pintype "passive"))
      (node (ref "R14") (pin "1") (pinfunction "1_1") (pintype "passive"))
      (node (ref "U1") (pin "37") (pinfunction "PA3/USART2_RX/TIM5_CH4/TIM9_CH2/TIM2_CH4/OTG_HS_ULPI_D0/ETH_MII_COL/ADC123_IN3_37") (pintype "bidirectional"))
    )
    (net (code "13") (name "/PA4{slash}D10{slash}SPI1_NSS") (class "Default")
      (node (ref "CON4") (pin "3") (pinfunction "3_3") (pintype "passive"))
      (node (ref "U1") (pin "40") (pinfunction "PA4/SPI1_NSS/SPI3_NSS/USART2_CK/DCMI_HSYNC/OTG_HS_SOF/I2S3_WS/ADC12_IN4/DAC1_OUT_40") (pintype "bidirectional"))
      (node (ref "U4") (pin "D10") (pinfunction "D10_D10") (pintype "bidirectional"))
    )
    (net (code "14") (name "/PA5{slash}D13{slash}SPI1_SCK") (class "Default")
      (node (ref "CON4") (pin "6") (pinfunction "6_6") (pintype "passive"))
      (node (ref "U1") (pin "41") (pinfunction "PA5/SPI1_SCK/OTG_HS_ULPI_CK/TIM2_CH1_ETR/TIM8_CHIN/ADC12_IN5/DAC2_OUT_41") (pintype "bidirectional"))
      (node (ref "U4") (pin "D13") (pinfunction "D13_D13") (pintype "bidirectional"))
    )
    (net (code "15") (name "/PA6{slash}D12{slash}SPI1_MISO") (class "Default")
      (node (ref "CON4") (pin "5") (pinfunction "5_5") (pintype "passive"))
      (node (ref "U1") (pin "42") (pinfunction "PA6/SPI1_MISO/TIM8_BKIN/TIM13_CH1/DCMI_PIXCLK/TIM3_CH1/TIM1_BKIN/ADC12_IN6_42") (pintype "bidirectional"))
      (node (ref "U4") (pin "D12") (pinfunction "D12_D12") (pintype "bidirectional"))
    )
    (net (code "16") (name "/PA7{slash}D11{slash}ETH_RMII_CRS_DV") (class "Default")
      (node (ref "RM2") (pin "3.2") (pinfunction "2_3.2") (pintype "passive"))
      (node (ref "U1") (pin "43") (pinfunction "PA7/SPI1_MOSI/TIM8_CH1N/TIM14_CH1/TIM3_CH2/ETH_MII_RX_DV/TIM1_CH1N/RMII_CRS_DV/ADC12_IN7_43") (pintype "bidirectional"))
      (node (ref "U3") (pin "15") (pinfunction "COL/CRS_DV/MODE2_15") (pintype "bidirectional"))
    )
    (net (code "17") (name "/PA8{slash}USB_HS_VBUSON") (class "Default")
      (node (ref "RM6") (pin "1.1") (pinfunction "1_1.1") (pintype "passive"))
      (node (ref "U1") (pin "100") (pinfunction "PA8/MCO1/USART1_CK/TIM1_CH1/I2C3_SCL/OTG_FS_SOF_100") (pintype "bidirectional"))
      (node (ref "U6") (pin "4") (pinfunction "ENB_4") (pintype "input"))
    )
    (net (code "18") (name "/PA9{slash}OTG_FS_VBUS") (class "Default")
      (node (ref "R37") (pin "1") (pinfunction "1.1_1") (pintype "passive"))
      (node (ref "U1") (pin "101") (pinfunction "PA9/USART1_TX/TIM1_CH2/I2C3_SMBA/DCMI_D0/OTG_FS_VBUS_101") (pintype "bidirectional"))
    )
    (net (code "19") (name "/PA10{slash}OTG1_FS_ID") (class "Default")
      (node (ref "D2") (pin "2") (pinfunction "2_2") (pintype "passive"))
      (node (ref "U1") (pin "102") (pinfunction "PA10/USART1_RX/TIM1_CH3/OTG_FS_ID/DCMI_D1_102") (pintype "bidirectional"))
      (node (ref "USB_OTG1") (pin "ID") (pinfunction "ID_ID") (pintype "input"))
    )
    (net (code "20") (name "/PA11{slash}OTG_FS_DM") (class "Default")
      (node (ref "C38") (pin "1") (pinfunction "1_1") (pintype "passive"))
      (node (ref "R38") (pin "1") (pinfunction "1_1") (pintype "passive"))
      (node (ref "U1") (pin "103") (pinfunction "PA11/USART1_CTS/CAN1_RX/TIM1_CH4/OTG_FS_DM_103") (pintype "bidirectional"))
    )
    (net (code "21") (name "/PA12{slash}OTG_FS_DP") (class "Default")
      (node (ref "C39") (pin "1") (pinfunction "1_1") (pintype "passive"))
      (node (ref "R39") (pin "1") (pinfunction "1_1") (pintype "passive"))
      (node (ref "U1") (pin "104") (pinfunction "PA12/USART1_RTS/CAN1_TX/TIM1_ETR/OTG_FS_DP_104") (pintype "bidirectional"))
    )
    (net (code "22") (name "/PA13{slash}TMS") (class "Default")
      (node (ref "JTAG") (pin "7") (pinfunction "7_7") (pintype "passive"))
      (node (ref "RM3") (pin "3.1") (pinfunction "1_3.1") (pintype "passive"))
      (node (ref "U1") (pin "105") (pinfunction "PA13/JTMS-SWDIO_105") (pintype "bidirectional"))
    )
    (net (code "23") (name "/PA14{slash}TCK") (class "Default")
      (node (ref "JTAG") (pin "9") (pinfunction "9_9") (pintype "passive"))
      (node (ref "RM3") (pin "2.2") (pinfunction "2_2.2") (pintype "passive"))
      (node (ref "U1") (pin "109") (pinfunction "PA14/JTCK-SWCLK_109") (pintype "bidirectional"))
    )
    (net (code "24") (name "/PA15{slash}TDI") (class "Default")
      (node (ref "JTAG") (pin "5") (pinfunction "5_5") (pintype "passive"))
      (node (ref "RM3") (pin "1.1") (pinfunction "1_1.1") (pintype "passive"))
      (node (ref "U1") (pin "110") (pinfunction "PA15/JTDI/SPI3_NSS/I2S3_WS/TIM2_CH1_ETR/SPI1_NSS_110") (pintype "bidirectional"))
    )
    (net (code "25") (name "/PB0{slash}USB_FS_VBUSON") (class "Default")
      (node (ref "RM6") (pin "4.1") (pinfunction "1_4.1") (pintype "passive"))
      (node (ref "U1") (pin "46") (pinfunction "PB0/TIM3_CH3/TIM8_CH2N/OTG_HS_ULPI_D1/ETH_MII_RXD2/TIM1_CH2N/ADC12_IN8_46") (pintype "bidirectional"))
      (node (ref "U6") (pin "1") (pinfunction "ENA_1") (pintype "input"))
    )
    (net (code "26") (name "/PB1{slash}USB_FS_FAULT") (class "Default")
      (node (ref "RM6") (pin "3.1") (pinfunction "1_3.1") (pintype "passive"))
      (node (ref "U1") (pin "47") (pinfunction "PB1/TIM3_CH4/TIM8_CH3N/OTG_HS_ULPI_D2/ETH_MII_RXD3/OTG_HS_INTN/TIM1_CH3N/ADC12_IN9_47") (pintype "bidirectional"))
      (node (ref "U6") (pin "2") (pinfunction "FLAG_A_2") (pintype "open_collector"))
    )
    (net (code "27") (name "/PB2") (class "Default")
      (node (ref "R3") (pin "1") (pinfunction "1_1") (pintype "passive"))
      (node (ref "U1") (pin "48") (pinfunction "PB2/BOOT1_48") (pintype "bidirectional"))
    )
    (net (code "28") (name "/PB3{slash}TDO") (class "Default")
      (node (ref "JTAG") (pin "13") (pinfunction "13_13") (pintype "passive"))
      (node (ref "R34") (pin "1") (pinfunction "1_1") (pintype "passive"))
      (node (ref "U1") (pin "133") (pinfunction "PB3/JTDO/TRACESWO/SPI3_SCK/I2S3_CK/TIM2_CH2/SPI1_SCK_133") (pintype "bidirectional"))
    )
    (net (code "29") (name "/PB4{slash}TRST") (class "Default")
      (node (ref "JTAG") (pin "3") (pinfunction "3_3") (pintype "passive"))
      (node (ref "R-T") (pin "1") (pinfunction "1_1") (pintype "passive"))
      (node (ref "RM3") (pin "4.1") (pinfunction "1_4.1") (pintype "passive"))
      (node (ref "U1") (pin "134") (pinfunction "PB4/NJTRST/SPI3_MISO/TIM3_CH1/SPI1_MISO_134") (pintype "bidirectional"))
    )
    (net (code "30") (name "/PB5{slash}D11{slash}SPI1_MOSI") (class "Default")
      (node (ref "CON4") (pin "4") (pinfunction "4_4") (pintype "passive"))
      (node (ref "U1") (pin "135") (pinfunction "PB5/I2C1_SMBA/CAN2_RX/OTG_HS_ULPI_D7/ETH_PPS_OUT/TIM3_CH2/SPI1_MOSI/SPI3_MOSI/DCMI_D10/I2S3_SD_135") (pintype "bidirectional"))
      (node (ref "U4") (pin "D11") (pinfunction "D11_D11") (pintype "bidirectional"))
    )
    (net (code "31") (name "/PB6{slash}D1{slash}USART1_TX") (class "Default")
      (node (ref "CON3") (pin "2") (pinfunction "2_2") (pintype "passive"))
      (node (ref "U1") (pin "136") (pinfunction "PB6/I2C1_SCL/TIM4_CH1/CAN2_TX/OTG_FS_INTN/DCMI_D5/USART1_TX_136") (pintype "bidirectional"))
      (node (ref "U4") (pin "D1") (pinfunction "D1_D1") (pintype "bidirectional"))
    )
    (net (code "32") (name "/PB8{slash}I2C1_SCL") (class "Default")
      (node (ref "R17") (pin "1") (pinfunction "1_1") (pintype "passive"))
      (node (ref "U1") (pin "139") (pinfunction "PB8/TIM4_CH3/SDIO_D4/TIM10_CH1/DCMI_D6/OTG_FS_SCL/ETH_MII_TXD3/I2C1_SCL/CAN1_RX_139") (pintype "bidirectional"))
      (node (ref "UEXT") (pin "5") (pinfunction "5_5") (pintype "passive"))
    )
    (net (code "33") (name "/PB9{slash}I2C1_SDA") (class "Default")
      (node (ref "R18") (pin "1") (pinfunction "1_1") (pintype "passive"))
      (node (ref "U1") (pin "140") (pinfunction "PB9/SPI2_NSS/I2S2_WS/TIM4_CH4/TIM11_CH1/OTG_FS_SDA/SDIO_D5/DCMI_D7/I2C1_SDA/CAN1_TX_140") (pintype "bidirectional"))
      (node (ref "UEXT") (pin "6") (pinfunction "6_6") (pintype "passive"))
    )
    (net (code "34") (name "/PB10{slash}SPI2_SCK{slash}UART3_TX") (class "Default")
      (node (ref "BOOT") (pin "1") (pinfunction "1_1") (pintype "passive"))
      (node (ref "U1") (pin "69") (pinfunction "PB10/SPI2_SCK/I2S2_CK/I2C2_SCL/USART3_TX/OTG_HS_ULPI_D3/ETH_MII_RX_ER/OTG_HS_SCL/TIM2_CH3_69") (pintype "bidirectional"))
      (node (ref "UEXT") (pin "9") (pinfunction "9_9") (pintype "passive"))
    )
    (net (code "35") (name "/PB12{slash}OTG2_HS_ID") (class "Default")
      (node (ref "D3") (pin "2") (pinfunction "2_2") (pintype "passive"))
      (node (ref "U1") (pin "73") (pinfunction "PB12/SPI2_NSS/I2S2_WS/I2C2_SMBA/USART3_CK/TIM1_BKIN/CAN2_RX/OTG_HS_ULPI_D5/ETH_RMII_TXD0/ETH_MII_TXD0/OTG_HS_ID_73") (pintype "bidirectional"))
      (node (ref "USB_OTG2") (pin "ID") (pinfunction "ID_ID") (pintype "input"))
    )
    (net (code "36") (name "/PB13{slash}OTG_HS_VBUS") (class "Default")
      (node (ref "R40") (pin "1") (pinfunction "1.1_1") (pintype "passive"))
      (node (ref "U1") (pin "74") (pinfunction "PB13/SPI2_SCK/I2S2_CK/USART3_CTS/TIM1_CH1N/CAN2_TX/OTG_HS_ULPI_D6/ETH_RMII_TXD1/ETH_MII_TXD1/OTG_HS_VBUS_74") (pintype "bidirectional"))
    )
    (net (code "37") (name "/PB14{slash}OTG_HS_DM") (class "Default")
      (node (ref "C45") (pin "1") (pinfunction "1_1") (pintype "passive"))
      (node (ref "R42") (pin "1") (pinfunction "1_1") (pintype "passive"))
      (node (ref "U1") (pin "75") (pinfunction "PB14/SPI2_MISO/TIM1_CH2N/TIM12_CH1/OTG_HS_DM/USART3_RTS/TIM8_CH2N_75") (pintype "bidirectional"))
    )
    (net (code "38") (name "/PB15{slash}OTG_HS_DP") (class "Default")
      (node (ref "C44") (pin "1") (pinfunction "1_1") (pintype "passive"))
      (node (ref "R41") (pin "1") (pinfunction "1_1") (pintype "passive"))
      (node (ref "U1") (pin "76") (pinfunction "PB15/SPI2_MOSI/I2S2_SD/TIM1_CH3N/TIM8_CH3N/TIM12_CH2/OTG_HS_DP_76") (pintype "bidirectional"))
    )
    (net (code "39") (name "/PC0{slash}A0") (class "Default")
      (node (ref "CON2") (pin "1") (pinfunction "1_1") (pintype "passive"))
      (node (ref "U1") (pin "26") (pinfunction "PC0/OTG_HS_ULPI_STP/ADC123_IN10_26") (pintype "bidirectional"))
      (node (ref "U4") (pin "A0") (pinfunction "A0_A0") (pintype "bidirectional"))
    )
    (net (code "40") (name "/PC1{slash}ETH_RMII_MDC") (class "Default")
      (node (ref "U1") (pin "27") (pinfunction "PC1/ETH_MDC/ADC123_IN11_27") (pintype "bidirectional"))
      (node (ref "U3") (pin "17") (pinfunction "MDC_17") (pintype "input"))
    )
    (net (code "41") (name "/PC2{slash}SPI2_MISO") (class "Default")
      (node (ref "U1") (pin "28") (pinfunction "PC2/SPI2_MISO/OTG_HS_ULPI_DIR/ETH_MII_TXD2/ADC123_IN12_28") (pintype "bidirectional"))
      (node (ref "UEXT") (pin "7") (pinfunction "7_7") (pintype "passive"))
    )
    (net (code "42") (name "/PC3{slash}SPI2_MOSI") (class "Default")
      (node (ref "R19") (pin "1") (pinfunction "1_1") (pintype "passive"))
      (node (ref "U1") (pin "29") (pinfunction "PC3/SPI2_MOSI/I2S2_SD/OTG_HS_ULPI_NXT/ETH_MII_TX_CLK/ADC123_IN13_29") (pintype "bidirectional"))
      (node (ref "UEXT") (pin "8") (pinfunction "8_8") (pintype "passive"))
    )
    (net (code "43") (name "/PC4{slash}ETH_RMII_RXD0") (class "Default")
      (node (ref "RM2") (pin "2.2") (pinfunction "2_2.2") (pintype "passive"))
      (node (ref "U1") (pin "44") (pinfunction "PC4/ETH_RMII_RX_D0/ETH_MII_RX_D0/ADC12_IN14_44") (pintype "bidirectional"))
      (node (ref "U3") (pin "11") (pinfunction "RXD0/MODE0_11") (pintype "bidirectional"))
    )
    (net (code "44") (name "/PC5{slash}ETH_RMII_RXD1") (class "Default")
      (node (ref "RM2") (pin "1.2") (pinfunction "2_1.2") (pintype "passive"))
      (node (ref "U1") (pin "45") (pinfunction "PC5/ETH_RMII_RX_D1/ETH_MII_RX_D1/ADC12_IN15_45") (pintype "bidirectional"))
      (node (ref "U3") (pin "10") (pinfunction "RXD1/MODE1_10") (pintype "bidirectional"))
    )
    (net (code "45") (name "/PC6{slash}USART6_TX") (class "Default")
      (node (ref "U1") (pin "96") (pinfunction "PC6/SPI2_MCK/TIM8_CH1/SDIO_D6/USART6_TX/DCMI_D0/TIM3_CH1_96") (pintype "bidirectional"))
      (node (ref "UEXT") (pin "3") (pinfunction "3_3") (pintype "passive"))
    )
    (net (code "46") (name "/PC7{slash}USART6_RX") (class "Default")
      (node (ref "U1") (pin "97") (pinfunction "PC7/SPI3_MCK/TIM8_CH2/SDIO_D7/USART6_RX/DCMI_D1/TIM3_CH2_97") (pintype "bidirectional"))
      (node (ref "UEXT") (pin "4") (pinfunction "4_4") (pintype "passive"))
    )
    (net (code "47") (name "/PC8{slash}SD_D0") (class "Default")
      (node (ref "RM1") (pin "2.1") (pinfunction "1_2.1") (pintype "passive"))
      (node (ref "SD/MMC") (pin "7") (pinfunction "DAT0/DO_7") (pintype "output"))
      (node (ref "U1") (pin "98") (pinfunction "PC8/TIM8_CH3/SDIO_D0/TIM3_CH3/USART6_CK/DCMI_D2_98") (pintype "bidirectional"))
    )
    (net (code "48") (name "/PC9{slash}SD_D1") (class "Default")
      (node (ref "RM1") (pin "1.1") (pinfunction "1_1.1") (pintype "passive"))
      (node (ref "SD/MMC") (pin "8") (pinfunction "DAT1/RES_8") (pintype "bidirectional"))
      (node (ref "U1") (pin "99") (pinfunction "PC9/I2S2_CKIN/I2S3_CKIN/MCO2/TIM8_CH4/SDIO_D1/I2C3_SDA/DCMI_D3/TIM3_CH4_99") (pintype "bidirectional"))
    )
    (net (code "49") (name "/PC10{slash}SD_D2") (class "Default")
      (node (ref "RM1") (pin "4.1") (pinfunction "1_4.1") (pintype "passive"))
      (node (ref "SD/MMC") (pin "1") (pinfunction "DAT2/RES_1") (pintype "bidirectional"))
      (node (ref "U1") (pin "111") (pinfunction "PC10/SPI3_SCK/I2S3_CK/UART4_TX/SDIO_D2/DCMI_D8/USART3_TX_111") (pintype "bidirectional"))
    )
    (net (code "50") (name "/PC11{slash}SD_D3") (class "Default")
      (node (ref "R11") (pin "2") (pinfunction "2_2") (pintype "passive"))
      (node (ref "R12") (pin "1") (pinfunction "1_1") (pintype "passive"))
      (node (ref "SD/MMC") (pin "2") (pinfunction "CD/DAT3/CS_2") (pintype "input"))
      (node (ref "U1") (pin "112") (pinfunction "PC11/UART4_RX/SPI3_MISO/SDIO_D3/DCMI_D4/USART3_RX_112") (pintype "bidirectional"))
    )
    (net (code "51") (name "/PC12{slash}SD_CLK") (class "Default")
      (node (ref "SD/MMC") (pin "5") (pinfunction "CLK/SCLK_5") (pintype "input"))
      (node (ref "U1") (pin "113") (pinfunction "PC12/UART5_TX/SDIO_CK/DCMI_D9/SPI3_MOSI/I2S3_SD/USART3_CK_113") (pintype "bidirectional"))
    )
    (net (code "52") (name "/PD0") (class "Default")
      (node (ref "PD") (pin "3") (pinfunction "3_3") (pintype "passive"))
      (node (ref "U1") (pin "114") (pinfunction "PD0/FSMC_D2/CAN1_RX_114") (pintype "bidirectional"))
    )
    (net (code "53") (name "/PD1") (class "Default")
      (node (ref "PD") (pin "4") (pinfunction "4_4") (pintype "passive"))
      (node (ref "U1") (pin "115") (pinfunction "PD1/FSMC_D3/CAN1_TX_115") (pintype "bidirectional"))
    )
    (net (code "54") (name "/PD2{slash}SD_CMD") (class "Default")
      (node (ref "R36") (pin "2") (pinfunction "2_2") (pintype "passive"))
      (node (ref "RM1") (pin "3.1") (pinfunction "1_3.1") (pintype "passive"))
      (node (ref "SD/MMC") (pin "3") (pinfunction "CMD/DI_3") (pintype "input"))
      (node (ref "U1") (pin "116") (pinfunction "PD2/TIM3_ETR/UART5_RX/SDIO_CMD/DCMI_D11_116") (pintype "bidirectional"))
    )
    (net (code "55") (name "/PD3") (class "Default")
      (node (ref "PD") (pin "6") (pinfunction "6_6") (pintype "passive"))
      (node (ref "U1") (pin "117") (pinfunction "PD3/FSMC_CLK/USART2_CTS_117") (pintype "bidirectional"))
    )
    (net (code "56") (name "/PD4") (class "Default")
      (node (ref "PD") (pin "7") (pinfunction "7_7") (pintype "passive"))
      (node (ref "U1") (pin "118") (pinfunction "PD4/FSMC_NOE/USART2_RTS_118") (pintype "bidirectional"))
    )
    (net (code "57") (name "/PD5") (class "Default")
      (node (ref "PD") (pin "8") (pinfunction "8_8") (pintype "passive"))
      (node (ref "U1") (pin "119") (pinfunction "PD5/FSMC_NWE/USART2_TX_119") (pintype "bidirectional"))
    )
    (net (code "58") (name "/PD6") (class "Default")
      (node (ref "PD") (pin "9") (pinfunction "9_9") (pintype "passive"))
      (node (ref "U1") (pin "122") (pinfunction "PD6/FSMC_NWAIT/USART2_RX_122") (pintype "bidirectional"))
    )
    (net (code "59") (name "/PD7") (class "Default")
      (node (ref "PD") (pin "10") (pinfunction "10_10") (pintype "passive"))
      (node (ref "U1") (pin "123") (pinfunction "PD7/USART2_CK/FSMC_NE1/FSMC_NCE2_123") (pintype "bidirectional"))
    )
    (net (code "60") (name "/PD8") (class "Default")
      (node (ref "PD") (pin "11") (pinfunction "11_11") (pintype "passive"))
      (node (ref "U1") (pin "77") (pinfunction "PD8/FSMC_D13/USART3_TX_77") (pintype "bidirectional"))
    )
    (net (code "61") (name "/PD9") (class "Default")
      (node (ref "PD") (pin "12") (pinfunction "12_12") (pintype "passive"))
      (node (ref "U1") (pin "78") (pinfunction "PD9/FSMC_D14/USART3_RX_78") (pintype "bidirectional"))
    )
    (net (code "62") (name "/PD10") (class "Default")
      (node (ref "PD") (pin "13") (pinfunction "13_13") (pintype "passive"))
      (node (ref "U1") (pin "79") (pinfunction "PD10/FSMC_D15/USART3_CK_79") (pintype "bidirectional"))
    )
    (net (code "63") (name "/PD11") (class "Default")
      (node (ref "PD") (pin "14") (pinfunction "14_14") (pintype "passive"))
      (node (ref "U1") (pin "80") (pinfunction "PD11/FSMC_A16/USART3_CTS_80") (pintype "bidirectional"))
    )
    (net (code "64") (name "/PD12") (class "Default")
      (node (ref "PD") (pin "15") (pinfunction "15_15") (pintype "passive"))
      (node (ref "U1") (pin "81") (pinfunction "PD12/FSMC_A17/TIM4_CH1/USART3_RTS_81") (pintype "bidirectional"))
    )
    (net (code "65") (name "/PD13") (class "Default")
      (node (ref "PD") (pin "16") (pinfunction "16_16") (pintype "passive"))
      (node (ref "U1") (pin "82") (pinfunction "PD13/FSMC_A18/TIM4_CH2_82") (pintype "bidirectional"))
    )
    (net (code "66") (name "/PD14") (class "Default")
      (node (ref "PD") (pin "17") (pinfunction "17_17") (pintype "passive"))
      (node (ref "U1") (pin "85") (pinfunction "PD14/FSMC_D0/TIM4_CH3_85") (pintype "bidirectional"))
    )
    (net (code "67") (name "/PD15") (class "Default")
      (node (ref "PD") (pin "18") (pinfunction "18_18") (pintype "passive"))
      (node (ref "U1") (pin "86") (pinfunction "PD15/FSMC_D1/TIM4_CH4_86") (pintype "bidirectional"))
    )
    (net (code "68") (name "/PE0") (class "Default")
      (node (ref "PE") (pin "3") (pinfunction "3_3") (pintype "passive"))
      (node (ref "U1") (pin "141") (pinfunction "PE0/TIM4_ETR/FSMC_NBL0/DCMI_D2_141") (pintype "bidirectional"))
    )
    (net (code "69") (name "/PE1") (class "Default")
      (node (ref "PE") (pin "4") (pinfunction "4_4") (pintype "passive"))
      (node (ref "U1") (pin "142") (pinfunction "PE1/FSMC_NBL1/DCMI_D3_142") (pintype "bidirectional"))
    )
    (net (code "70") (name "/PE2{slash}D2") (class "Default")
      (node (ref "CON3") (pin "3") (pinfunction "3_3") (pintype "passive"))
      (node (ref "PE2_E") (pin "1") (pinfunction "1_1") (pintype "passive"))
      (node (ref "U1") (pin "1") (pinfunction "PE2/TRACECK/FSMC_A23/ETH_MII_TXD3_1") (pintype "bidirectional"))
      (node (ref "U4") (pin "D2") (pinfunction "D2_D2") (pintype "bidirectional"))
    )
    (net (code "71") (name "/PE3") (class "Default")
      (node (ref "PE") (pin "6") (pinfunction "6_6") (pintype "passive"))
      (node (ref "U1") (pin "2") (pinfunction "PE3/TRACED0/FSMC_A19_2") (pintype "bidirectional"))
    )
    (net (code "72") (name "/PE4{slash}D3") (class "Default")
      (node (ref "CON3") (pin "4") (pinfunction "4_4") (pintype "passive"))
      (node (ref "PE4_E") (pin "1") (pinfunction "1_1") (pintype "passive"))
      (node (ref "U1") (pin "3") (pinfunction "PE4/TRACED1/FSMC_A20/DCMI_D4_3") (pintype "bidirectional"))
      (node (ref "U4") (pin "D3") (pinfunction "D3_D3") (pintype "bidirectional"))
    )
    (net (code "73") (name "/PE5{slash}D4") (class "Default")
      (node (ref "CON3") (pin "5") (pinfunction "5_5") (pintype "passive"))
      (node (ref "PE5_E") (pin "2") (pinfunction "2_2") (pintype "passive"))
      (node (ref "U1") (pin "4") (pinfunction "PE5/TRACED2/FSMC_A21/TIM9_CH1/DCMI_D6_4") (pintype "bidirectional"))
      (node (ref "U4") (pin "D4") (pinfunction "D4_D4") (pintype "bidirectional"))
    )
    (net (code "74") (name "/PE6{slash}D5") (class "Default")
      (node (ref "CON3") (pin "6") (pinfunction "6_6") (pintype "passive"))
      (node (ref "PE6_E") (pin "1") (pinfunction "1_1") (pintype "passive"))
      (node (ref "U1") (pin "5") (pinfunction "PE6/TRACED3/FSMC_A22/TIM9_CH2/DCMI_D7_5") (pintype "bidirectional"))
      (node (ref "U4") (pin "D5") (pinfunction "D5_D5") (pintype "bidirectional"))
    )
    (net (code "75") (name "/PE7") (class "Default")
      (node (ref "PE") (pin "10") (pinfunction "10_10") (pintype "passive"))
      (node (ref "U1") (pin "58") (pinfunction "PE7/FSMC_D4/TIM1_ETR_58") (pintype "bidirectional"))
    )
    (net (code "76") (name "/PE8") (class "Default")
      (node (ref "PE") (pin "11") (pinfunction "11_11") (pintype "passive"))
      (node (ref "U1") (pin "59") (pinfunction "PE8/FSMC_D5/TIM1_CH1N_59") (pintype "bidirectional"))
    )
    (net (code "77") (name "/PE9") (class "Default")
      (node (ref "PE") (pin "12") (pinfunction "12_12") (pintype "passive"))
      (node (ref "U1") (pin "60") (pinfunction "PE9/FSMC_D6/TIM1_CH1_60") (pintype "bidirectional"))
    )
    (net (code "78") (name "/PE10") (class "Default")
      (node (ref "PE") (pin "13") (pinfunction "13_13") (pintype "passive"))
      (node (ref "U1") (pin "63") (pinfunction "PE10/FSMC_D7/TIM1_CH2N_63") (pintype "bidirectional"))
    )
    (net (code "79") (name "/PE11") (class "Default")
      (node (ref "PE") (pin "14") (pinfunction "14_14") (pintype "passive"))
      (node (ref "U1") (pin "64") (pinfunction "PE11/FSMC_D8/TIM1_CH2_64") (pintype "bidirectional"))
    )
    (net (code "80") (name "/PE12") (class "Default")
      (node (ref "PE") (pin "15") (pinfunction "15_15") (pintype "passive"))
      (node (ref "U1") (pin "65") (pinfunction "PE12/FSMC_D9/TIM1_CH3N_65") (pintype "bidirectional"))
    )
    (net (code "81") (name "/PE13") (class "Default")
      (node (ref "PE") (pin "16") (pinfunction "16_16") (pintype "passive"))
      (node (ref "U1") (pin "66") (pinfunction "PE13/FSMC_D10/TIM1_CH3_66") (pintype "bidirectional"))
    )
    (net (code "82") (name "/PE14") (class "Default")
      (node (ref "PE") (pin "17") (pinfunction "17_17") (pintype "passive"))
      (node (ref "U1") (pin "67") (pinfunction "PE14/FSMC_D11/TIM1_CH4_67") (pintype "bidirectional"))
    )
    (net (code "83") (name "/PE15") (class "Default")
      (node (ref "PE") (pin "18") (pinfunction "18_18") (pintype "passive"))
      (node (ref "U1") (pin "68") (pinfunction "PE15/FSMC_D12/TIM1_BKIN_68") (pintype "bidirectional"))
    )
    (net (code "84") (name "/PF0") (class "Default")
      (node (ref "PF") (pin "3") (pinfunction "3_3") (pintype "passive"))
      (node (ref "U1") (pin "10") (pinfunction "PF0/FSMC_A0/I2C2_SDA_10") (pintype "bidirectional"))
    )
    (net (code "85") (name "/PF1") (class "Default")
      (node (ref "PF") (pin "4") (pinfunction "4_4") (pintype "passive"))
      (node (ref "U1") (pin "11") (pinfunction "PF1/FSMC_A1/I2C2_SCL_11") (pintype "bidirectional"))
    )
    (net (code "86") (name "/PF2") (class "Default")
      (node (ref "PF") (pin "5") (pinfunction "5_5") (pintype "passive"))
      (node (ref "U1") (pin "12") (pinfunction "PF2/FSMC_A2/I2C2_SMBA_12") (pintype "bidirectional"))
    )
    (net (code "87") (name "/PF3") (class "Default")
      (node (ref "PF") (pin "6") (pinfunction "6_6") (pintype "passive"))
      (node (ref "U1") (pin "13") (pinfunction "PF3/FSMC_A3/ADC3_IN9_13") (pintype "bidirectional"))
    )
    (net (code "88") (name "/PF4") (class "Default")
      (node (ref "PF") (pin "7") (pinfunction "7_7") (pintype "passive"))
      (node (ref "U1") (pin "14") (pinfunction "PF4/FSMC_A4/ADC3_IN14_14") (pintype "bidirectional"))
    )
    (net (code "89") (name "/PF5") (class "Default")
      (node (ref "PF") (pin "8") (pinfunction "8_8") (pintype "passive"))
      (node (ref "U1") (pin "15") (pinfunction "PF5/FSMC_A5/ADC3_IN15_15") (pintype "bidirectional"))
    )
    (net (code "90") (name "/PF6{slash}A1") (class "Default")
      (node (ref "CON2") (pin "2") (pinfunction "2_2") (pintype "passive"))
      (node (ref "PF6_E") (pin "1") (pinfunction "1_1") (pintype "passive"))
      (node (ref "U1") (pin "18") (pinfunction "PF6/TIM10_CH1/FSMC_NIORD/ADC3_IN4_18") (pintype "bidirectional"))
      (node (ref "U4") (pin "A1") (pinfunction "A1_A1") (pintype "bidirectional"))
    )
    (net (code "91") (name "/PF7{slash}A2") (class "Default")
      (node (ref "CON2") (pin "3") (pinfunction "3_3") (pintype "passive"))
      (node (ref "PF7_E") (pin "2") (pinfunction "2_2") (pintype "passive"))
      (node (ref "U1") (pin "19") (pinfunction "PF7/TIM11_CH1/FSMC_NREG/ADC3_IN5_19") (pintype "bidirectional"))
      (node (ref "U4") (pin "A2") (pinfunction "A2_A2") (pintype "bidirectional"))
    )
    (net (code "92") (name "/PF9{slash}A4") (class "Default")
      (node (ref "CON2") (pin "5") (pinfunction "5_5") (pintype "passive"))
      (node (ref "PF9_E") (pin "2") (pinfunction "2_2") (pintype "passive"))
      (node (ref "R16") (pin "1") (pinfunction "1_1") (pintype "passive"))
      (node (ref "U1") (pin "21") (pinfunction "PF9/TIM14_CH1/FSMC_CD/ADC3_IN7_21") (pintype "bidirectional"))
      (node (ref "U4") (pin "A4") (pinfunction "A4_A4") (pintype "bidirectional"))
    )
    (net (code "93") (name "/PF10{slash}A5") (class "Default")
      (node (ref "CON2") (pin "6") (pinfunction "6_6") (pintype "passive"))
      (node (ref "PF10_E") (pin "1") (pinfunction "1_1") (pintype "passive"))
      (node (ref "R15") (pin "1") (pinfunction "1_1") (pintype "passive"))
      (node (ref "U1") (pin "22") (pinfunction "PF10/FSMC_INTR/ADC3_IN8_22") (pintype "bidirectional"))
      (node (ref "U4") (pin "A5") (pinfunction "A5_A5") (pintype "bidirectional"))
    )
    (net (code "94") (name "/PF11{slash}USB_HS_FAULT") (class "Default")
      (node (ref "PF11_E") (pin "2") (pinfunction "2_2") (pintype "passive"))
      (node (ref "RM6") (pin "2.1") (pinfunction "1_2.1") (pintype "passive"))
      (node (ref "U1") (pin "49") (pinfunction "PF11/DCMI_12_49") (pintype "bidirectional"))
      (node (ref "U6") (pin "3") (pinfunction "FLAG_B_3") (pintype "open_collector"))
    )
    (net (code "95") (name "/PF12") (class "Default")
      (node (ref "PF") (pin "15") (pinfunction "15_15") (pintype "passive"))
      (node (ref "U1") (pin "50") (pinfunction "PF12/FSMC_A6_50") (pintype "bidirectional"))
    )
    (net (code "96") (name "/PF13") (class "Default")
      (node (ref "PF") (pin "16") (pinfunction "16_16") (pintype "passive"))
      (node (ref "U1") (pin "53") (pinfunction "PF13/FSMC_A7_53") (pintype "bidirectional"))
    )
    (net (code "97") (name "/PF14") (class "Default")
      (node (ref "PF") (pin "17") (pinfunction "17_17") (pintype "passive"))
      (node (ref "U1") (pin "54") (pinfunction "PF14/FSMC_A8_54") (pintype "bidirectional"))
    )
    (net (code "98") (name "/PF15") (class "Default")
      (node (ref "PF") (pin "18") (pinfunction "18_18") (pintype "passive"))
      (node (ref "U1") (pin "55") (pinfunction "PF15/FSMC_A9_55") (pintype "bidirectional"))
    )
    (net (code "99") (name "/PG0") (class "Default")
      (node (ref "PG") (pin "3") (pinfunction "3_3") (pintype "passive"))
      (node (ref "U1") (pin "56") (pinfunction "PG0/FSMC_A10_56") (pintype "bidirectional"))
    )
    (net (code "100") (name "/PG1") (class "Default")
      (node (ref "PG") (pin "4") (pinfunction "4_4") (pintype "passive"))
      (node (ref "U1") (pin "57") (pinfunction "PG1/FSMC_A11_57") (pintype "bidirectional"))
    )
    (net (code "101") (name "/PG2") (class "Default")
      (node (ref "PG") (pin "5") (pinfunction "5_5") (pintype "passive"))
      (node (ref "U1") (pin "87") (pinfunction "PG2/FSMC_A12_87") (pintype "bidirectional"))
    )
    (net (code "102") (name "/PG3") (class "Default")
      (node (ref "PG") (pin "6") (pinfunction "6_6") (pintype "passive"))
      (node (ref "U1") (pin "88") (pinfunction "PG3/FSMC_A13_88") (pintype "bidirectional"))
    )
    (net (code "103") (name "/PG4") (class "Default")
      (node (ref "PG") (pin "7") (pinfunction "7_7") (pintype "passive"))
      (node (ref "U1") (pin "89") (pinfunction "PG4/FSMC_A14_89") (pintype "bidirectional"))
    )
    (net (code "104") (name "/PG5") (class "Default")
      (node (ref "PG") (pin "8") (pinfunction "8_8") (pintype "passive"))
      (node (ref "U1") (pin "90") (pinfunction "PG5/FSMC_A15_90") (pintype "bidirectional"))
    )
    (net (code "105") (name "/PG6{slash}EPHY-RST#") (class "Default")
      (node (ref "PG") (pin "9") (pinfunction "9_9") (pintype "passive"))
      (node (ref "R27") (pin "1") (pinfunction "1_1") (pintype "passive"))
      (node (ref "U1") (pin "91") (pinfunction "PG6/FSMC_INT2_91") (pintype "bidirectional"))
    )
    (net (code "106") (name "/PG7{slash}D6") (class "Default")
      (node (ref "CON3") (pin "7") (pinfunction "7_7") (pintype "passive"))
      (node (ref "PG7_E") (pin "2") (pinfunction "2_2") (pintype "passive"))
      (node (ref "U1") (pin "92") (pinfunction "PG7/FSMC_INT3/USART6_CK_92") (pintype "bidirectional"))
      (node (ref "U4") (pin "D6") (pinfunction "D6_D6") (pintype "bidirectional"))
    )
    (net (code "107") (name "/PG8{slash}D7") (class "Default")
      (node (ref "CON3") (pin "8") (pinfunction "8_8") (pintype "passive"))
      (node (ref "PG8_E") (pin "1") (pinfunction "1_1") (pintype "passive"))
      (node (ref "U1") (pin "93") (pinfunction "PG8/USART6_RTS/ETH_PPS_OUT_93") (pintype "bidirectional"))
      (node (ref "U4") (pin "D7") (pinfunction "D7_D7") (pintype "bidirectional"))
    )
    (net (code "108") (name "/PG9") (class "Default")
      (node (ref "PG") (pin "12") (pinfunction "12_12") (pintype "passive"))
      (node (ref "U1") (pin "124") (pinfunction "PG9/USART6_RX/FSMC_NE2/FSMC_NCE3_124") (pintype "bidirectional"))
    )
    (net (code "109") (name "/PG10{slash}UEXT_CS") (class "Default")
      (node (ref "R43") (pin "2") (pinfunction "2_2") (pintype "passive"))
      (node (ref "U1") (pin "125") (pinfunction "PG10/FSMC_NCE4_1/FSMC_NE3_125") (pintype "bidirectional"))
      (node (ref "UEXT") (pin "10") (pinfunction "10_10") (pintype "passive"))
    )
    (net (code "110") (name "/PG11{slash}ETH_RMII_TX_EN") (class "Default")
      (node (ref "R44") (pin "1") (pinfunction "1_1") (pintype "passive"))
      (node (ref "U1") (pin "126") (pinfunction "PG11/FSMC_NCE4_2/ETH_MII_TX_EN_126") (pintype "bidirectional"))
      (node (ref "U3") (pin "21") (pinfunction "TXEN_21") (pintype "input"))
    )
    (net (code "111") (name "/PG12{slash}D8") (class "Default")
      (node (ref "CON4") (pin "1") (pinfunction "1_1") (pintype "passive"))
      (node (ref "PG12_E") (pin "1") (pinfunction "1_1") (pintype "passive"))
      (node (ref "U1") (pin "127") (pinfunction "PG12/FSMC_NE4/USART6_RTS_127") (pintype "bidirectional"))
      (node (ref "U4") (pin "D8") (pinfunction "D8_D8") (pintype "bidirectional"))
    )
    (net (code "112") (name "/PG13{slash}ETH_RMII_TXD0") (class "Default")
      (node (ref "R45") (pin "1") (pinfunction "1_1") (pintype "passive"))
      (node (ref "U1") (pin "128") (pinfunction "PG13/FSMC_A24/USART6_CTS/ETH_MII_TXD0/ETH_RMII_TXD0_128") (pintype "bidirectional"))
      (node (ref "U3") (pin "22") (pinfunction "TXD0_22") (pintype "input"))
    )
    (net (code "113") (name "/PG14{slash}ETH_RMII_TXD1") (class "Default")
      (node (ref "R46") (pin "2") (pinfunction "2_2") (pintype "passive"))
      (node (ref "U1") (pin "129") (pinfunction "PG14/FSMC_A25/USART6_TX/ETH_MII_TXD1/ETH_RMII_TXD1_129") (pintype "bidirectional"))
      (node (ref "U3") (pin "23") (pinfunction "TXD1_23") (pintype "input"))
    )
    (net (code "114") (name "/PG15{slash}D9") (class "Default")
      (node (ref "CON4") (pin "2") (pinfunction "2_2") (pintype "passive"))
      (node (ref "PG15_E") (pin "2") (pinfunction "2_2") (pintype "passive"))
      (node (ref "U1") (pin "132") (pinfunction "PG15/USART6_CTS/DCMI_D13_132") (pintype "bidirectional"))
      (node (ref "U4") (pin "D9") (pinfunction "D9_D9") (pintype "bidirectional"))
    )
    (net (code "115") (name "/PHYAD0") (class "Default")
      (node (ref "RM4") (pin "1.1") (pinfunction "1_1.1") (pintype "passive"))
      (node (ref "U3") (pin "13") (pinfunction "RXER/RXD4/PHYAD0_13") (pintype "bidirectional"))
    )
    (net (code "116") (name "/PHYAD1") (class "Default")
      (node (ref "RM4") (pin "3.1") (pinfunction "1_3.1") (pintype "passive"))
      (node (ref "U3") (pin "7") (pinfunction "RXCLK/PHYAD1_7") (pintype "bidirectional"))
    )
    (net (code "117") (name "/PHYAD2") (class "Default")
      (node (ref "RM4") (pin "2.1") (pinfunction "1_2.1") (pintype "passive"))
      (node (ref "U3") (pin "8") (pinfunction "RXD3/PHYAD2_8") (pintype "bidirectional"))
    )
    (net (code "118") (name "/RB7{slash}D0{slash}USART1_RX") (class "Default")
      (node (ref "CON3") (pin "1") (pinfunction "1_1") (pintype "passive"))
      (node (ref "U1") (pin "137") (pinfunction "PB7/I2C1_SDA/FSMC_NL/DCMI_VSYNC/USART1_RX/TIM4_CH2_137") (pintype "bidirectional"))
      (node (ref "U4") (pin "D0") (pinfunction "D0_D0") (pintype "bidirectional"))
    )
    (net (code "119") (name "/RB11{slash}UART3_RX") (class "Default")
      (node (ref "BOOT") (pin "2") (pinfunction "2_2") (pintype "passive"))
      (node (ref "R54") (pin "1") (pinfunction "1_1") (pintype "passive"))
      (node (ref "U1") (pin "70") (pinfunction "PB11/I2C2_SDA/USART3_RX/OTG_HS_ULPI_D4/ETH_RMII_TX_EN/ETH_MII_TX_EN/OTG_HS_SDA/TIM2_CH4_70") (pintype "bidirectional"))
    )
    (net (code "120") (name "/RF8{slash}A3") (class "Default")
      (node (ref "CON2") (pin "4") (pinfunction "4_4") (pintype "passive"))
      (node (ref "PF8_E") (pin "1") (pinfunction "1_1") (pintype "passive"))
      (node (ref "U1") (pin "20") (pinfunction "PF8/TIM13_CH1/FSMC_NIOWR/ADC3_IN6_20") (pintype "bidirectional"))
      (node (ref "U4") (pin "A3") (pinfunction "A3_A3") (pintype "bidirectional"))
    )
    (net (code "121") (name "/RMIISEL") (class "Default")
      (node (ref "RM4") (pin "4.1") (pinfunction "1_4.1") (pintype "passive"))
      (node (ref "U3") (pin "9") (pinfunction "RXD2/RMIISEL_9") (pintype "bidirectional"))
    )
    (net (code "122") (name "/RST") (class "Default")
      (node (ref "CON1") (pin "1") (pinfunction "1_1") (pintype "passive"))
      (node (ref "JTAG") (pin "15") (pinfunction "15_15") (pintype "passive"))
      (node (ref "R-T") (pin "2") (pinfunction "2_2") (pintype "passive"))
      (node (ref "R8") (pin "1") (pinfunction "1_1") (pintype "passive"))
      (node (ref "U1") (pin "25") (pinfunction "NRST_25") (pintype "power_in"))
      (node (ref "U4") (pin "RST") (pinfunction "RST_RST") (pintype "bidirectional"))
    )
    (net (code "123") (name "/USB_OTG1_D+") (class "Default")
      (node (ref "U5") (pin "3") (pinfunction "3_3") (pintype "bidirectional"))
      (node (ref "USB_OTG1") (pin "D+") (pinfunction "D+_D+") (pintype "input"))
    )
    (net (code "124") (name "/USB_OTG1_D-") (class "Default")
      (node (ref "U5") (pin "1") (pinfunction "1_1") (pintype "bidirectional"))
      (node (ref "USB_OTG1") (pin "D-") (pinfunction "D-_D-") (pintype "input"))
    )
    (net (code "125") (name "/USB_OTG2_D+") (class "Default")
      (node (ref "U7") (pin "3") (pinfunction "3_3") (pintype "bidirectional"))
      (node (ref "USB_OTG2") (pin "D+") (pinfunction "D+_D+") (pintype "input"))
    )
    (net (code "126") (name "/USB_OTG2_D-") (class "Default")
      (node (ref "U7") (pin "1") (pinfunction "1_1") (pintype "bidirectional"))
      (node (ref "USB_OTG2") (pin "D-") (pinfunction "D-_D-") (pintype "input"))
    )
    (net (code "127") (name "/VBAT") (class "Default")
      (node (ref "D1") (pin "3") (pinfunction "K_3") (pintype "passive"))
      (node (ref "U1") (pin "6") (pinfunction "VBAT_6") (pintype "power_in"))
    )
    (net (code "128") (name "3.3V") (class "Default")
      (node (ref "3.3V_E") (pin "2") (pinfunction "2_2") (pintype "passive"))
      (node (ref "B0_1/B0_1") (pin "1") (pinfunction "1_1") (pintype "passive"))
      (node (ref "B1_1/B1_1") (pin "1") (pinfunction "1_1") (pintype "passive"))
      (node (ref "BOOT") (pin "4") (pinfunction "4_4") (pintype "passive"))
      (node (ref "C10") (pin "2") (pinfunction "2_2") (pintype "passive"))
      (node (ref "C11") (pin "2") (pinfunction "2_2") (pintype "passive"))
      (node (ref "C12") (pin "2") (pinfunction "2_2") (pintype "passive"))
      (node (ref "C13") (pin "2") (pinfunction "2_2") (pintype "passive"))
      (node (ref "C14") (pin "2") (pinfunction "2_2") (pintype "passive"))
      (node (ref "C2") (pin "2") (pinfunction "2_2") (pintype "passive"))
      (node (ref "C26") (pin "2") (pinfunction "2_2") (pintype "passive"))
      (node (ref "C27") (pin "2") (pinfunction "2_2") (pintype "passive"))
      (node (ref "C28") (pin "2") (pinfunction "2_2") (pintype "passive"))
      (node (ref "C29") (pin "2") (pinfunction "2_2") (pintype "passive"))
      (node (ref "C3") (pin "2") (pinfunction "2_2") (pintype "passive"))
      (node (ref "C35") (pin "2") (pinfunction "2_2") (pintype "passive"))
      (node (ref "C40") (pin "2") (pinfunction "2_2") (pintype "passive"))
      (node (ref "C46") (pin "2") (pinfunction "2_2") (pintype "passive"))
      (node (ref "C5") (pin "2") (pinfunction "2_2") (pintype "passive"))
      (node (ref "C6") (pin "2") (pinfunction "2_2") (pintype "passive"))
      (node (ref "C7") (pin "2") (pinfunction "2_2") (pintype "passive"))
      (node (ref "C8") (pin "2") (pinfunction "2_2") (pintype "passive"))
      (node (ref "C9") (pin "2") (pinfunction "2_2") (pintype "passive"))
      (node (ref "CD1") (pin "4") (pinfunction "VDD_4") (pintype "power_in"))
      (node (ref "CON1") (pin "2") (pinfunction "2_2") (pintype "passive"))
      (node (ref "D1") (pin "1") (pinfunction "A1_1") (pintype "passive"))
      (node (ref "JTAG") (pin "1") (pinfunction "1_1") (pintype "passive"))
      (node (ref "JTAG") (pin "2") (pinfunction "2_2") (pintype "passive"))
      (node (ref "L1") (pin "1") (pinfunction "1_1") (pintype "passive"))
      (node (ref "L2") (pin "1") (pinfunction "1_1") (pintype "passive"))
      (node (ref "L3") (pin "2") (pinfunction "2_2") (pintype "passive"))
      (node (ref "PD") (pin "1") (pinfunction "1_1") (pintype "passive"))
      (node (ref "PE") (pin "1") (pinfunction "1_1") (pintype "passive"))
      (node (ref "PF") (pin "1") (pinfunction "1_1") (pintype "passive"))
      (node (ref "PG") (pin "1") (pinfunction "1_1") (pintype "passive"))
      (node (ref "R1") (pin "2") (pinfunction "1.2_2") (pintype "passive"))
      (node (ref "R11") (pin "1") (pinfunction "1_1") (pintype "passive"))
      (node (ref "R13") (pin "2") (pinfunction "2_2") (pintype "passive"))
      (node (ref "R15") (pin "2") (pinfunction "2_2") (pintype "passive"))
      (node (ref "R16") (pin "2") (pinfunction "2_2") (pintype "passive"))
      (node (ref "R17") (pin "2") (pinfunction "2_2") (pintype "passive"))
      (node (ref "R18") (pin "2") (pinfunction "2_2") (pintype "passive"))
      (node (ref "R19") (pin "2") (pinfunction "2_2") (pintype "passive"))
      (node (ref "R26") (pin "2") (pinfunction "2_2") (pintype "passive"))
      (node (ref "R28") (pin "1") (pinfunction "1_1") (pintype "passive"))
      (node (ref "R33") (pin "2") (pinfunction "2_2") (pintype "passive"))
      (node (ref "R34") (pin "2") (pinfunction "2_2") (pintype "passive"))
      (node (ref "R35") (pin "1") (pinfunction "1_1") (pintype "passive"))
      (node (ref "R50") (pin "1") (pinfunction "1_1") (pintype "passive"))
      (node (ref "R54") (pin "2") (pinfunction "2_2") (pintype "passive"))
      (node (ref "R6") (pin "2") (pinfunction "2_2") (pintype "passive"))
      (node (ref "RM1") (pin "1.2") (pinfunction "2_1.2") (pintype "passive"))
      (node (ref "RM1") (pin "2.2") (pinfunction "2_2.2") (pintype "passive"))
      (node (ref "RM1") (pin "3.2") (pinfunction "2_3.2") (pintype "passive"))
      (node (ref "RM1") (pin "4.2") (pinfunction "2_4.2") (pintype "passive"))
      (node (ref "RM2") (pin "1.1") (pinfunction "1_1.1") (pintype "passive"))
      (node (ref "RM2") (pin "2.1") (pinfunction "1_2.1") (pintype "passive"))
      (node (ref "RM2") (pin "3.1") (pinfunction "1_3.1") (pintype "passive"))
      (node (ref "RM2") (pin "4.1") (pinfunction "1_4.1") (pintype "passive"))
      (node (ref "RM3") (pin "1.2") (pinfunction "2_1.2") (pintype "passive"))
      (node (ref "RM3") (pin "3.2") (pinfunction "2_3.2") (pintype "passive"))
      (node (ref "RM3") (pin "4.2") (pinfunction "2_4.2") (pintype "passive"))
      (node (ref "RM4") (pin "4.2") (pinfunction "2_4.2") (pintype "passive"))
      (node (ref "RM6") (pin "2.2") (pinfunction "2_2.2") (pintype "passive"))
      (node (ref "RM6") (pin "3.2") (pinfunction "2_3.2") (pintype "passive"))
      (node (ref "U1") (pin "108") (pinfunction "VDD_2_108") (pintype "power_in"))
      (node (ref "U1") (pin "121") (pinfunction "VDD_10_121") (pintype "power_in"))
      (node (ref "U1") (pin "131") (pinfunction "VDD_11_131") (pintype "power_in"))
      (node (ref "U1") (pin "144") (pinfunction "VDD_SA_144") (pintype "power_in"))
      (node (ref "U1") (pin "17") (pinfunction "VDD_5_17") (pintype "power_in"))
      (node (ref "U1") (pin "30") (pinfunction "VDD_12_30") (pintype "power_in"))
      (node (ref "U1") (pin "39") (pinfunction "VDD_4_39") (pintype "power_in"))
      (node (ref "U1") (pin "52") (pinfunction "VDD_6_52") (pintype "power_in"))
      (node (ref "U1") (pin "62") (pinfunction "VDD_7_62") (pintype "power_in"))
      (node (ref "U1") (pin "72") (pinfunction "VDD_1_72") (pintype "power_in"))
      (node (ref "U1") (pin "84") (pinfunction "VDD_8_84") (pintype "power_in"))
      (node (ref "U1") (pin "95") (pinfunction "VDD_9_95") (pintype "power_in"))
      (node (ref "U2") (pin "2") (pinfunction "VCC_2") (pintype "power_in"))
      (node (ref "U3") (pin "12") (pinfunction "VDDIO_12") (pintype "power_in"))
      (node (ref "U4") (pin "3V3") (pinfunction "3V3_3V3") (pintype "bidirectional"))
      (node (ref "U5") (pin "5") (pinfunction "5_5") (pintype "power_in"))
      (node (ref "U7") (pin "5") (pinfunction "5_5") (pintype "power_in"))
      (node (ref "UEXT") (pin "1") (pinfunction "1_1") (pintype "passive"))
      (node (ref "WKUP") (pin "P$1") (pinfunction "0_P$1") (pintype "passive"))
    )
    (net (code "129") (name "3.3V_A") (class "Default")
      (node (ref "AREF_EN") (pin "1") (pinfunction "1_1") (pintype "passive"))
      (node (ref "C16") (pin "1") (pinfunction "1_1") (pintype "passive"))
      (node (ref "C17") (pin "2") (pinfunction "2_2") (pintype "passive"))
      (node (ref "L1") (pin "2") (pinfunction "2_2") (pintype "passive"))
      (node (ref "U1") (pin "33") (pinfunction "VDDA_33") (pintype "power_in"))
    )
    (net (code "130") (name "AGND") (class "Default")
      (node (ref "AGND_E") (pin "1") (pinfunction "1_1") (pintype "passive"))
      (node (ref "C16") (pin "2") (pinfunction "2_2") (pintype "passive"))
      (node (ref "C17") (pin "1") (pinfunction "1_1") (pintype "passive"))
      (node (ref "C18") (pin "1") (pinfunction "1_1") (pintype "passive"))
      (node (ref "CON4") (pin "7") (pinfunction "7_7") (pintype "passive"))
      (node (ref "U1") (pin "31") (pinfunction "VSSA_31") (pintype "power_in"))
      (node (ref "U4") (pin "GND@2") (pinfunction "GND_GND@2") (pintype "bidirectional"))
    )
    (net (code "131") (name "GND") (class "Default")
      (node (ref "3V_BAT") (pin "2") (pinfunction "2_2") (pintype "passive"))
      (node (ref "AGND_E") (pin "2") (pinfunction "2_2") (pintype "passive"))
      (node (ref "B0_1/B0_1") (pin "3") (pinfunction "3_3") (pintype "passive"))
      (node (ref "B1_1/B1_1") (pin "3") (pinfunction "3_3") (pintype "passive"))
      (node (ref "BOOT") (pin "3") (pinfunction "3_3") (pintype "passive"))
      (node (ref "C1") (pin "1") (pinfunction "1_1") (pintype "passive"))
      (node (ref "C10") (pin "1") (pinfunction "1_1") (pintype "passive"))
      (node (ref "C11") (pin "1") (pinfunction "1_1") (pintype "passive"))
      (node (ref "C12") (pin "1") (pinfunction "1_1") (pintype "passive"))
      (node (ref "C13") (pin "1") (pinfunction "1_1") (pintype "passive"))
      (node (ref "C14") (pin "1") (pinfunction "1_1") (pintype "passive"))
      (node (ref "C15") (pin "1") (pinfunction "1_1") (pintype "passive"))
      (node (ref "C19") (pin "2") (pinfunction "2_2") (pintype "passive"))
      (node (ref "C2") (pin "1") (pinfunction "1_1") (pintype "passive"))
      (node (ref "C20") (pin "2") (pinfunction "2_2") (pintype "passive"))
      (node (ref "C21") (pin "2") (pinfunction "2_2") (pintype "passive"))
      (node (ref "C22") (pin "1") (pinfunction "1_1") (pintype "passive"))
      (node (ref "C23") (pin "2") (pinfunction "2_2") (pintype "passive"))
      (node (ref "C24") (pin "2") (pinfunction "2_2") (pintype "passive"))
      (node (ref "C25") (pin "2") (pinfunction "2_2") (pintype "passive"))
      (node (ref "C26") (pin "1") (pinfunction "1_1") (pintype "passive"))
      (node (ref "C27") (pin "1") (pinfunction "1_1") (pintype "passive"))
      (node (ref "C28") (pin "1") (pinfunction "1_1") (pintype "passive"))
      (node (ref "C29") (pin "1") (pinfunction "1_1") (pintype "passive"))
      (node (ref "C3") (pin "1") (pinfunction "1_1") (pintype "passive"))
      (node (ref "C30") (pin "1") (pinfunction "1_1") (pintype "passive"))
      (node (ref "C31") (pin "1") (pinfunction "1_1") (pintype "passive"))
      (node (ref "C32") (pin "1") (pinfunction "1_1") (pintype "passive"))
      (node (ref "C33") (pin "1") (pinfunction "1_1") (pintype "passive"))
      (node (ref "C34") (pin "1") (pinfunction "1_1") (pintype "passive"))
      (node (ref "C36") (pin "1") (pinfunction "1_1") (pintype "passive"))
      (node (ref "C37") (pin "1") (pinfunction "1_1") (pintype "passive"))
      (node (ref "C38") (pin "2") (pinfunction "2_2") (pintype "passive"))
      (node (ref "C39") (pin "2") (pinfunction "2_2") (pintype "passive"))
      (node (ref "C4") (pin "1") (pinfunction "1_1") (pintype "passive"))
      (node (ref "C40") (pin "1") (pinfunction "1_1") (pintype "passive"))
      (node (ref "C41") (pin "-") (pinfunction "-_-") (pintype "passive"))
      (node (ref "C42") (pin "2") (pinfunction "2_2") (pintype "passive"))
      (node (ref "C43") (pin "2") (pinfunction "2_2") (pintype "passive"))
      (node (ref "C44") (pin "2") (pinfunction "2_2") (pintype "passive"))
      (node (ref "C45") (pin "2") (pinfunction "2_2") (pintype "passive"))
      (node (ref "C46") (pin "1") (pinfunction "1_1") (pintype "passive"))
      (node (ref "C47") (pin "-") (pinfunction "-_-") (pintype "passive"))
      (node (ref "C48") (pin "2") (pinfunction "2_2") (pintype "passive"))
      (node (ref "C5") (pin "1") (pinfunction "1_1") (pintype "passive"))
      (node (ref "C52") (pin "-") (pinfunction "-_-") (pintype "passive"))
      (node (ref "C53") (pin "2") (pinfunction "2_2") (pintype "passive"))
      (node (ref "C54") (pin "-") (pinfunction "-_-") (pintype "passive"))
      (node (ref "C55") (pin "2") (pinfunction "2_2") (pintype "passive"))
      (node (ref "C56") (pin "2") (pinfunction "2_2") (pintype "passive"))
      (node (ref "C57") (pin "2") (pinfunction "2_2") (pintype "passive"))
      (node (ref "C58") (pin "-") (pinfunction "-_-") (pintype "passive"))
      (node (ref "C59") (pin "2") (pinfunction "2_2") (pintype "passive"))
      (node (ref "C6") (pin "1") (pinfunction "1_1") (pintype "passive"))
      (node (ref "C60") (pin "2") (pinfunction "2_2") (pintype "passive"))
      (node (ref "C61") (pin "2") (pinfunction "2_2") (pintype "passive"))
      (node (ref "C7") (pin "1") (pinfunction "1_1") (pintype "passive"))
      (node (ref "C8") (pin "1") (pinfunction "1_1") (pintype "passive"))
      (node (ref "C9") (pin "1") (pinfunction "1_1") (pintype "passive"))
      (node (ref "CD1") (pin "2") (pinfunction "VSS_2") (pintype "power_in"))
      (node (ref "CON1") (pin "4") (pinfunction "4_4") (pintype "passive"))
      (node (ref "CON1") (pin "5") (pinfunction "5_5") (pintype "passive"))
      (node (ref "D2") (pin "3") (pinfunction "3_3") (pintype "passive"))
      (node (ref "D3") (pin "3") (pinfunction "3_3") (pintype "passive"))
      (node (ref "D4") (pin "A") (pinfunction "A_A") (pintype "passive"))
      (node (ref "GND_PIN") (pin "P$1") (pinfunction "PP_P$1") (pintype "passive"))
      (node (ref "JTAG") (pin "10") (pinfunction "10_10") (pintype "passive"))
      (node (ref "JTAG") (pin "12") (pinfunction "12_12") (pintype "passive"))
      (node (ref "JTAG") (pin "14") (pinfunction "14_14") (pintype "passive"))
      (node (ref "JTAG") (pin "16") (pinfunction "16_16") (pintype "passive"))
      (node (ref "JTAG") (pin "18") (pinfunction "18_18") (pintype "passive"))
      (node (ref "JTAG") (pin "20") (pinfunction "20_20") (pintype "passive"))
      (node (ref "JTAG") (pin "4") (pinfunction "4_4") (pintype "passive"))
      (node (ref "JTAG") (pin "6") (pinfunction "6_6") (pintype "passive"))
      (node (ref "JTAG") (pin "8") (pinfunction "8_8") (pintype "passive"))
      (node (ref "L4") (pin "1") (pinfunction "1_1") (pintype "passive"))
      (node (ref "L5") (pin "1") (pinfunction "1_1") (pintype "passive"))
      (node (ref "LAN") (pin "GND1") (pinfunction "GND1_GND1") (pintype "input"))
      (node (ref "LAN") (pin "GND2") (pinfunction "GND2_GND2") (pintype "input"))
      (node (ref "PD") (pin "2") (pinfunction "2_2") (pintype "passive"))
      (node (ref "PD") (pin "20") (pinfunction "20_20") (pintype "passive"))
      (node (ref "PE") (pin "2") (pinfunction "2_2") (pintype "passive"))
      (node (ref "PE") (pin "20") (pinfunction "20_20") (pintype "passive"))
      (node (ref "PF") (pin "2") (pinfunction "2_2") (pintype "passive"))
      (node (ref "PF") (pin "20") (pinfunction "20_20") (pintype "passive"))
      (node (ref "PG") (pin "2") (pinfunction "2_2") (pintype "passive"))
      (node (ref "PG") (pin "20") (pinfunction "20_20") (pintype "passive"))
      (node (ref "PWR_JACK") (pin "-") (pinfunction "-_-") (pintype "passive"))
      (node (ref "PWR_JACK") (pin "--") (pinfunction "--_--") (pintype "passive"))
      (node (ref "PWR_LED") (pin "C") (pinfunction "C_C") (pintype "passive"))
      (node (ref "Q2") (pin "GND") (pinfunction "GND_GND") (pintype "bidirectional"))
      (node (ref "R12") (pin "2") (pinfunction "2_2") (pintype "passive"))
      (node (ref "R2") (pin "2") (pinfunction "2_2") (pintype "passive"))
      (node (ref "R29") (pin "1") (pinfunction "1_1") (pintype "passive"))
      (node (ref "R31") (pin "2") (pinfunction "2_2") (pintype "passive"))
      (node (ref "R32") (pin "1") (pinfunction "1_1") (pintype "passive"))
      (node (ref "R51") (pin "2") (pinfunction "2_2") (pintype "passive"))
      (node (ref "R52") (pin "2") (pinfunction "2_2") (pintype "passive"))
      (node (ref "R53") (pin "2") (pinfunction "2_2") (pintype "passive"))
      (node (ref "RESET") (pin "P$2") (pinfunction "1_P$2") (pintype "passive"))
      (node (ref "RM3") (pin "2.1") (pinfunction "1_2.1") (pintype "passive"))
      (node (ref "RM4") (pin "1.2") (pinfunction "2_1.2") (pintype "passive"))
      (node (ref "RM4") (pin "2.2") (pinfunction "2_2.2") (pintype "passive"))
      (node (ref "RM4") (pin "3.2") (pinfunction "2_3.2") (pintype "passive"))
      (node (ref "RM5") (pin "1.2") (pinfunction "2_1.2") (pintype "passive"))
      (node (ref "RM5") (pin "2.2") (pinfunction "2_2.2") (pintype "passive"))
      (node (ref "RM5") (pin "3.2") (pinfunction "2_3.2") (pintype "passive"))
      (node (ref "RM6") (pin "1.2") (pinfunction "2_1.2") (pintype "passive"))
      (node (ref "RM6") (pin "4.2") (pinfunction "2_4.2") (pintype "passive"))
      (node (ref "SD/MMC") (pin "6") (pinfunction "VSS_6") (pintype "power_in"))
      (node (ref "U1") (pin "107") (pinfunction "VSS_2_107") (pintype "power_in"))
      (node (ref "U1") (pin "120") (pinfunction "VSS_10_120") (pintype "power_in"))
      (node (ref "U1") (pin "130") (pinfunction "VSS_11_130") (pintype "power_in"))
      (node (ref "U1") (pin "16") (pinfunction "VSS_5_16") (pintype "power_in"))
      (node (ref "U1") (pin "38") (pinfunction "VSS_4_38") (pintype "power_in"))
      (node (ref "U1") (pin "51") (pinfunction "VSS_6_51") (pintype "power_in"))
      (node (ref "U1") (pin "61") (pinfunction "VSS_7_61") (pintype "power_in"))
      (node (ref "U1") (pin "83") (pinfunction "VSS_8_83") (pintype "power_in"))
      (node (ref "U1") (pin "94") (pinfunction "VSS_9_94") (pintype "power_in"))
      (node (ref "U2") (pin "3") (pinfunction "GND_3") (pintype "power_in"))
      (node (ref "U3") (pin "24") (pinfunction "TXD2_24") (pintype "input"))
      (node (ref "U3") (pin "25") (pinfunction "TXD3_25") (pintype "input"))
      (node (ref "U3") (pin "EP1") (pinfunction "GND1_EP1") (pintype "input"))
      (node (ref "U3") (pin "EP2") (pinfunction "GND2_EP2") (pintype "input"))
      (node (ref "U3") (pin "EP3") (pinfunction "GND3_EP3") (pintype "input"))
      (node (ref "U3") (pin "EP4") (pinfunction "GND4_EP4") (pintype "input"))
      (node (ref "U3") (pin "EP5") (pinfunction "GND5_EP5") (pintype "input"))
      (node (ref "U3") (pin "EP6") (pinfunction "GND6_EP6") (pintype "input"))
      (node (ref "U3") (pin "EP7") (pinfunction "GND7_EP7") (pintype "input"))
      (node (ref "U3") (pin "EP8") (pinfunction "GND8_EP8") (pintype "input"))
      (node (ref "U3") (pin "EP9") (pinfunction "GND9_EP9") (pintype "input"))
      (node (ref "U3") (pin "EXP_PAD") (pinfunction "GND_EXP_PAD") (pintype "power_in"))
      (node (ref "U4") (pin "GND") (pinfunction "GND_GND") (pintype "bidirectional"))
      (node (ref "U4") (pin "GND@1") (pinfunction "GND_GND@1") (pintype "bidirectional"))
      (node (ref "U5") (pin "2") (pinfunction "2_2") (pintype "power_in"))
      (node (ref "U6") (pin "6") (pinfunction "GND_6") (pintype "power_in"))
      (node (ref "U7") (pin "2") (pinfunction "2_2") (pintype "power_in"))
      (node (ref "U8") (pin "4") (pinfunction "GND_4") (pintype "bidirectional"))
      (node (ref "U9") (pin "2") (pinfunction "GND_2") (pintype "bidirectional"))
      (node (ref "UEXT") (pin "2") (pinfunction "2_2") (pintype "passive"))
      (node (ref "USB_OTG1") (pin "GND") (pinfunction "GND_GND") (pintype "power_in"))
      (node (ref "USB_OTG2") (pin "GND") (pinfunction "GND_GND") (pintype "power_in"))
    )
    (net (code "132") (name "Net-(3.3V_E-Pad1)") (class "Default")
      (node (ref "3.3V_E") (pin "1") (pinfunction "1_1") (pintype "passive"))
      (node (ref "C51") (pin "1") (pinfunction "1_1") (pintype "passive"))
      (node (ref "C56") (pin "1") (pinfunction "1_1") (pintype "passive"))
      (node (ref "C57") (pin "1") (pinfunction "1_1") (pintype "passive"))
      (node (ref "C58") (pin "+") (pinfunction "+_+") (pintype "passive"))
      (node (ref "C59") (pin "1") (pinfunction "1_1") (pintype "passive"))
      (node (ref "L6") (pin "2") (pinfunction "2_2") (pintype "passive"))
      (node (ref "R49") (pin "1") (pinfunction "1_1") (pintype "passive"))
    )
    (net (code "133") (name "Net-(B0_1/B0_1-Pad2)") (class "Default")
      (node (ref "B0_1/B0_1") (pin "2") (pinfunction "2_2") (pintype "passive"))
      (node (ref "R5") (pin "2") (pinfunction "2_2") (pintype "passive"))
    )
    (net (code "134") (name "Net-(B1_1/B1_1-Pad2)") (class "Default")
      (node (ref "B1_1/B1_1") (pin "2") (pinfunction "2_2") (pintype "passive"))
      (node (ref "R3") (pin "2") (pinfunction "2_2") (pintype "passive"))
    )
    (net (code "135") (name "Net-(C20-Pad1)") (class "Default")
      (node (ref "C20") (pin "1") (pinfunction "1_1") (pintype "passive"))
      (node (ref "Q1") (pin "1") (pinfunction "1_1") (pintype "passive"))
      (node (ref "R9") (pin "1") (pinfunction "1_1") (pintype "passive"))
    )
    (net (code "136") (name "Net-(C50-Pad2)") (class "Default")
      (node (ref "C50") (pin "2") (pinfunction "2_2") (pintype "passive"))
      (node (ref "R51") (pin "1") (pinfunction "1_1") (pintype "passive"))
    )
    (net (code "137") (name "Net-(CD1-E{slash}D)") (class "Default")
      (node (ref "CD1") (pin "1") (pinfunction "E/D_1") (pintype "input"))
      (node (ref "R35") (pin "2") (pinfunction "2_2") (pintype "passive"))
    )
    (net (code "138") (name "Net-(D1-A2)") (class "Default")
      (node (ref "3V_BAT") (pin "1") (pinfunction "1_1") (pintype "passive"))
      (node (ref "D1") (pin "2") (pinfunction "A2_2") (pintype "passive"))
    )
    (net (code "139") (name "Net-(L4-Pad2)") (class "Default")
      (node (ref "L4") (pin "2") (pinfunction "2_2") (pintype "passive"))
      (node (ref "USB_OTG1") (pin "GND1") (pinfunction "GND1_GND1") (pintype "input"))
      (node (ref "USB_OTG1") (pin "GND2") (pinfunction "GND2_GND2") (pintype "input"))
      (node (ref "USB_OTG1") (pin "GND3") (pinfunction "GND3_GND3") (pintype "input"))
      (node (ref "USB_OTG1") (pin "GND4") (pinfunction "GND4_GND4") (pintype "input"))
    )
    (net (code "140") (name "Net-(L5-Pad2)") (class "Default")
      (node (ref "L5") (pin "2") (pinfunction "2_2") (pintype "passive"))
      (node (ref "USB_OTG2") (pin "GND1") (pinfunction "GND1_GND1") (pintype "input"))
      (node (ref "USB_OTG2") (pin "GND2") (pinfunction "GND2_GND2") (pintype "input"))
      (node (ref "USB_OTG2") (pin "GND3") (pinfunction "GND3_GND3") (pintype "input"))
      (node (ref "USB_OTG2") (pin "GND4") (pinfunction "GND4_GND4") (pintype "input"))
    )
    (net (code "141") (name "Net-(LAN-COM)") (class "Default")
      (node (ref "C37") (pin "2") (pinfunction "2_2") (pintype "passive"))
      (node (ref "LAN") (pin "3") (pinfunction "COM_3") (pintype "bidirectional"))
      (node (ref "LAN") (pin "6") (pinfunction "NC_6") (pintype "bidirectional"))
      (node (ref "R20") (pin "1") (pinfunction "1.1_1") (pintype "passive"))
    )
    (net (code "142") (name "Net-(LAN-PadAG)") (class "Default")
      (node (ref "LAN") (pin "AG") (pinfunction "AG_AG") (pintype "passive"))
      (node (ref "R21") (pin "2") (pinfunction "2_2") (pintype "passive"))
    )
    (net (code "143") (name "Net-(LAN-PadKY)") (class "Default")
      (node (ref "LAN") (pin "KY") (pinfunction "KY_KY") (pintype "passive"))
      (node (ref "R31") (pin "1") (pinfunction "1_1") (pintype "passive"))
    )
    (net (code "144") (name "Net-(LAN-RD+)") (class "Default")
      (node (ref "LAN") (pin "7") (pinfunction "RD+_7") (pintype "bidirectional"))
      (node (ref "R23") (pin "1") (pinfunction "1_1") (pintype "passive"))
      (node (ref "U3") (pin "31") (pinfunction "RXP_31") (pintype "input"))
    )
    (net (code "145") (name "Net-(LAN-RD-)") (class "Default")
      (node (ref "LAN") (pin "8") (pinfunction "RD-_8") (pintype "bidirectional"))
      (node (ref "R22") (pin "1") (pinfunction "1_1") (pintype "passive"))
      (node (ref "U3") (pin "30") (pinfunction "RXN_30") (pintype "input"))
    )
    (net (code "146") (name "Net-(LAN-TD+)") (class "Default")
      (node (ref "LAN") (pin "1") (pinfunction "TD+_1") (pintype "bidirectional"))
      (node (ref "R25") (pin "1") (pinfunction "1_1") (pintype "passive"))
      (node (ref "U3") (pin "29") (pinfunction "TXP_29") (pintype "output"))
    )
    (net (code "147") (name "Net-(LAN-TD-)") (class "Default")
      (node (ref "LAN") (pin "2") (pinfunction "TD-_2") (pintype "bidirectional"))
      (node (ref "R24") (pin "1") (pinfunction "1_1") (pintype "passive"))
      (node (ref "U3") (pin "28") (pinfunction "TXN_28") (pintype "output"))
    )
    (net (code "148") (name "Net-(LED-PadA)") (class "Default")
      (node (ref "LED") (pin "A") (pinfunction "A_A") (pintype "passive"))
      (node (ref "R26") (pin "1") (pinfunction "1_1") (pintype "passive"))
    )
    (net (code "149") (name "Net-(PD-Pad5)") (class "Default")
      (node (ref "PD") (pin "5") (pinfunction "5_5") (pintype "passive"))
      (node (ref "R36") (pin "1") (pinfunction "1_1") (pintype "passive"))
    )
    (net (code "150") (name "Net-(PE-Pad5)") (class "Default")
      (node (ref "PE") (pin "5") (pinfunction "5_5") (pintype "passive"))
      (node (ref "PE2_E") (pin "2") (pinfunction "2_2") (pintype "passive"))
    )
    (net (code "151") (name "Net-(PE-Pad7)") (class "Default")
      (node (ref "PE") (pin "7") (pinfunction "7_7") (pintype "passive"))
      (node (ref "PE4_E") (pin "2") (pinfunction "2_2") (pintype "passive"))
    )
    (net (code "152") (name "Net-(PE-Pad8)") (class "Default")
      (node (ref "PE") (pin "8") (pinfunction "8_8") (pintype "passive"))
      (node (ref "PE5_E") (pin "1") (pinfunction "1_1") (pintype "passive"))
    )
    (net (code "153") (name "Net-(PE-Pad9)") (class "Default")
      (node (ref "PE") (pin "9") (pinfunction "9_9") (pintype "passive"))
      (node (ref "PE6_E") (pin "2") (pinfunction "2_2") (pintype "passive"))
    )
    (net (code "154") (name "Net-(PF-Pad9)") (class "Default")
      (node (ref "PF") (pin "9") (pinfunction "9_9") (pintype "passive"))
      (node (ref "PF6_E") (pin "2") (pinfunction "2_2") (pintype "passive"))
    )
    (net (code "155") (name "Net-(PF-Pad10)") (class "Default")
      (node (ref "PF") (pin "10") (pinfunction "10_10") (pintype "passive"))
      (node (ref "PF7_E") (pin "1") (pinfunction "1_1") (pintype "passive"))
    )
    (net (code "156") (name "Net-(PF-Pad11)") (class "Default")
      (node (ref "PF") (pin "11") (pinfunction "11_11") (pintype "passive"))
      (node (ref "PF8_E") (pin "2") (pinfunction "2_2") (pintype "passive"))
    )
    (net (code "157") (name "Net-(PF-Pad12)") (class "Default")
      (node (ref "PF") (pin "12") (pinfunction "12_12") (pintype "passive"))
      (node (ref "PF9_E") (pin "1") (pinfunction "1_1") (pintype "passive"))
    )
    (net (code "158") (name "Net-(PF-Pad13)") (class "Default")
      (node (ref "PF") (pin "13") (pinfunction "13_13") (pintype "passive"))
      (node (ref "PF10_E") (pin "2") (pinfunction "2_2") (pintype "passive"))
    )
    (net (code "159") (name "Net-(PF-Pad14)") (class "Default")
      (node (ref "PF") (pin "14") (pinfunction "14_14") (pintype "passive"))
      (node (ref "PF11_E") (pin "1") (pinfunction "1_1") (pintype "passive"))
    )
    (net (code "160") (name "Net-(PG-Pad10)") (class "Default")
      (node (ref "PG") (pin "10") (pinfunction "10_10") (pintype "passive"))
      (node (ref "PG7_E") (pin "1") (pinfunction "1_1") (pintype "passive"))
    )
    (net (code "161") (name "Net-(PG-Pad11)") (class "Default")
      (node (ref "PG") (pin "11") (pinfunction "11_11") (pintype "passive"))
      (node (ref "PG8_E") (pin "2") (pinfunction "2_2") (pintype "passive"))
    )
    (net (code "162") (name "Net-(PG-Pad13)") (class "Default")
      (node (ref "PG") (pin "13") (pinfunction "13_13") (pintype "passive"))
      (node (ref "R43") (pin "1") (pinfunction "1_1") (pintype "passive"))
    )
    (net (code "163") (name "Net-(PG-Pad14)") (class "Default")
      (node (ref "PG") (pin "14") (pinfunction "14_14") (pintype "passive"))
      (node (ref "R44") (pin "2") (pinfunction "2_2") (pintype "passive"))
    )
    (net (code "164") (name "Net-(PG-Pad15)") (class "Default")
      (node (ref "PG") (pin "15") (pinfunction "15_15") (pintype "passive"))
      (node (ref "PG12_E") (pin "2") (pinfunction "2_2") (pintype "passive"))
    )
    (net (code "165") (name "Net-(PG-Pad16)") (class "Default")
      (node (ref "PG") (pin "16") (pinfunction "16_16") (pintype "passive"))
      (node (ref "R45") (pin "2") (pinfunction "2_2") (pintype "passive"))
    )
    (net (code "166") (name "Net-(PG-Pad17)") (class "Default")
      (node (ref "PG") (pin "17") (pinfunction "17_17") (pintype "passive"))
      (node (ref "R46") (pin "1") (pinfunction "1_1") (pintype "passive"))
    )
    (net (code "167") (name "Net-(PG-Pad18)") (class "Default")
      (node (ref "PG") (pin "18") (pinfunction "18_18") (pintype "passive"))
      (node (ref "PG15_E") (pin "1") (pinfunction "1_1") (pintype "passive"))
    )
    (net (code "168") (name "Net-(PWR_LED-PadA)") (class "Default")
      (node (ref "PWR_LED") (pin "A") (pinfunction "A_A") (pintype "passive"))
      (node (ref "R50") (pin "2") (pinfunction "2_2") (pintype "passive"))
    )
    (net (code "169") (name "Net-(R1-1.1)") (class "Default")
      (node (ref "C4") (pin "2") (pinfunction "2_2") (pintype "passive"))
      (node (ref "R1") (pin "1") (pinfunction "1.1_1") (pintype "passive"))
      (node (ref "R2") (pin "1") (pinfunction "1_1") (pintype "passive"))
      (node (ref "U1") (pin "143") (pinfunction "VDD_3_143") (pintype "power_in"))
    )
    (net (code "170") (name "Net-(R20-1.2)") (class "Default")
      (node (ref "C30") (pin "2") (pinfunction "2_2") (pintype "passive"))
      (node (ref "C31") (pin "2") (pinfunction "2_2") (pintype "passive"))
      (node (ref "C32") (pin "2") (pinfunction "2_2") (pintype "passive"))
      (node (ref "L3") (pin "1") (pinfunction "1_1") (pintype "passive"))
      (node (ref "R20") (pin "2") (pinfunction "1.2_2") (pintype "passive"))
      (node (ref "R21") (pin "1") (pinfunction "1_1") (pintype "passive"))
      (node (ref "R22") (pin "2") (pinfunction "2_2") (pintype "passive"))
      (node (ref "R23") (pin "2") (pinfunction "2_2") (pintype "passive"))
      (node (ref "R24") (pin "2") (pinfunction "2_2") (pintype "passive"))
      (node (ref "R25") (pin "2") (pinfunction "2_2") (pintype "passive"))
      (node (ref "U3") (pin "1") (pinfunction "VDD2A_1") (pintype "power_in"))
      (node (ref "U3") (pin "27") (pinfunction "VDD1A_27") (pintype "power_in"))
    )
    (net (code "171") (name "Net-(R38-Pad2)") (class "Default")
      (node (ref "R38") (pin "2") (pinfunction "2_2") (pintype "passive"))
      (node (ref "U5") (pin "6") (pinfunction "6_6") (pintype "bidirectional"))
    )
    (net (code "172") (name "Net-(R39-Pad2)") (class "Default")
      (node (ref "R39") (pin "2") (pinfunction "2_2") (pintype "passive"))
      (node (ref "U5") (pin "4") (pinfunction "4_4") (pintype "bidirectional"))
    )
    (net (code "173") (name "Net-(R41-Pad2)") (class "Default")
      (node (ref "R41") (pin "2") (pinfunction "2_2") (pintype "passive"))
      (node (ref "U7") (pin "4") (pinfunction "4_4") (pintype "bidirectional"))
    )
    (net (code "174") (name "Net-(R42-Pad2)") (class "Default")
      (node (ref "R42") (pin "2") (pinfunction "2_2") (pintype "passive"))
      (node (ref "U7") (pin "6") (pinfunction "6_6") (pintype "bidirectional"))
    )
    (net (code "175") (name "Net-(RESET-0)") (class "Default")
      (node (ref "C22") (pin "2") (pinfunction "2_2") (pintype "passive"))
      (node (ref "R6") (pin "1") (pinfunction "1_1") (pintype "passive"))
      (node (ref "R8") (pin "2") (pinfunction "2_2") (pintype "passive"))
      (node (ref "RESET") (pin "P$1") (pinfunction "0_P$1") (pintype "passive"))
      (node (ref "U2") (pin "1") (pinfunction "RESET_1") (pintype "output"))
    )
    (net (code "176") (name "Net-(RM5B-1)") (class "Default")
      (node (ref "JTAG") (pin "17") (pinfunction "17_17") (pintype "passive"))
      (node (ref "RM5") (pin "2.1") (pinfunction "1_2.1") (pintype "passive"))
    )
    (net (code "177") (name "Net-(RM5C-1)") (class "Default")
      (node (ref "JTAG") (pin "11") (pinfunction "11_11") (pintype "passive"))
      (node (ref "R33") (pin "1") (pinfunction "1_1") (pintype "passive"))
      (node (ref "RM5") (pin "3.1") (pinfunction "1_3.1") (pintype "passive"))
    )
    (net (code "178") (name "Net-(SD/MMC-VDD)") (class "Default")
      (node (ref "C24") (pin "1") (pinfunction "1_1") (pintype "passive"))
      (node (ref "C25") (pin "1") (pinfunction "1_1") (pintype "passive"))
      (node (ref "L2") (pin "2") (pinfunction "2_2") (pintype "passive"))
      (node (ref "SD/MMC") (pin "4") (pinfunction "VDD_4") (pintype "power_in"))
    )
    (net (code "179") (name "Net-(U1-PC14{slash}OSC32_IN)") (class "Default")
      (node (ref "C21") (pin "1") (pinfunction "1_1") (pintype "passive"))
      (node (ref "Q2") (pin "2") (pinfunction "2_2") (pintype "passive"))
      (node (ref "R10") (pin "2") (pinfunction "2_2") (pintype "passive"))
      (node (ref "U1") (pin "8") (pinfunction "PC14/OSC32_IN_8") (pintype "bidirectional"))
    )
    (net (code "180") (name "Net-(U1-PC15{slash}OSC32_OUT)") (class "Default")
      (node (ref "C23") (pin "1") (pinfunction "1_1") (pintype "passive"))
      (node (ref "Q2") (pin "1") (pinfunction "1_1") (pintype "passive"))
      (node (ref "R10") (pin "1") (pinfunction "1_1") (pintype "passive"))
      (node (ref "U1") (pin "9") (pinfunction "PC15/OSC32_OUT_9") (pintype "bidirectional"))
    )
    (net (code "181") (name "Net-(U1-PH0{slash}OSC_IN)") (class "Default")
      (node (ref "C19") (pin "1") (pinfunction "1_1") (pintype "passive"))
      (node (ref "Q1") (pin "2") (pinfunction "2_2") (pintype "passive"))
      (node (ref "R7") (pin "2") (pinfunction "2_2") (pintype "passive"))
      (node (ref "U1") (pin "23") (pinfunction "PH0/OSC_IN_23") (pintype "input"))
    )
    (net (code "182") (name "Net-(U1-PH1{slash}OSC_OUT)") (class "Default")
      (node (ref "R7") (pin "1") (pinfunction "1_1") (pintype "passive"))
      (node (ref "R9") (pin "2") (pinfunction "2_2") (pintype "passive"))
      (node (ref "U1") (pin "24") (pinfunction "PH1/OSC_OUT_24") (pintype "output"))
    )
    (net (code "183") (name "Net-(U1-VCAP_1)") (class "Default")
      (node (ref "C1") (pin "2") (pinfunction "2_2") (pintype "passive"))
      (node (ref "U1") (pin "71") (pinfunction "VCAP_1_71") (pintype "output"))
    )
    (net (code "184") (name "Net-(U1-VCAP_2)") (class "Default")
      (node (ref "C15") (pin "2") (pinfunction "2_2") (pintype "passive"))
      (node (ref "U1") (pin "106") (pinfunction "VCAP_2_106") (pintype "output"))
    )
    (net (code "185") (name "Net-(U1-VREF+)") (class "Default")
      (node (ref "C18") (pin "2") (pinfunction "2_2") (pintype "passive"))
      (node (ref "R4") (pin "2") (pinfunction "2_2") (pintype "passive"))
      (node (ref "U1") (pin "32") (pinfunction "VREF+_32") (pintype "power_in"))
    )
    (net (code "186") (name "Net-(U3-LED1{slash}REGOFF)") (class "Default")
      (node (ref "LAN") (pin "AY") (pinfunction "AY_AY") (pintype "passive"))
      (node (ref "U3") (pin "3") (pinfunction "LED1/REGOFF_3") (pintype "bidirectional"))
    )
    (net (code "187") (name "Net-(U3-LED2{slash}NINTSEL)") (class "Default")
      (node (ref "LAN") (pin "KG") (pinfunction "KG_KG") (pintype "passive"))
      (node (ref "U3") (pin "2") (pinfunction "LED2/NINTSEL_2") (pintype "bidirectional"))
    )
    (net (code "188") (name "Net-(U3-NINT{slash}TXER{slash}TXD4)") (class "Default")
      (node (ref "R14") (pin "2") (pinfunction "2_2") (pintype "passive"))
      (node (ref "U3") (pin "18") (pinfunction "NINT/TXER/TXD4_18") (pintype "bidirectional"))
    )
    (net (code "189") (name "Net-(U3-NRST)") (class "Default")
      (node (ref "C36") (pin "2") (pinfunction "2_2") (pintype "passive"))
      (node (ref "R27") (pin "2") (pinfunction "2_2") (pintype "passive"))
      (node (ref "R28") (pin "2") (pinfunction "2_2") (pintype "passive"))
      (node (ref "U3") (pin "19") (pinfunction "NRST_19") (pintype "input"))
    )
    (net (code "190") (name "Net-(U3-RBIAS)") (class "Default")
      (node (ref "R29") (pin "2") (pinfunction "2_2") (pintype "passive"))
      (node (ref "U3") (pin "32") (pinfunction "RBIAS_32") (pintype "input"))
    )
    (net (code "191") (name "Net-(U3-VDDCR)") (class "Default")
      (node (ref "C33") (pin "2") (pinfunction "2_2") (pintype "passive"))
      (node (ref "C34") (pin "2") (pinfunction "2_2") (pintype "passive"))
      (node (ref "U3") (pin "6") (pinfunction "VDDCR_6") (pintype "power_in"))
    )
    (net (code "192") (name "Net-(U8-BS)") (class "Default")
      (node (ref "C49") (pin "1") (pinfunction "1_1") (pintype "passive"))
      (node (ref "U8") (pin "1") (pinfunction "BS_1") (pintype "bidirectional"))
    )
    (net (code "193") (name "Net-(U8-COMP)") (class "Default")
      (node (ref "C50") (pin "1") (pinfunction "1_1") (pintype "passive"))
      (node (ref "U8") (pin "6") (pinfunction "COMP_6") (pintype "bidirectional"))
    )
    (net (code "194") (name "Net-(U8-EN)") (class "Default")
      (node (ref "R47") (pin "2") (pinfunction "2_2") (pintype "passive"))
      (node (ref "U8") (pin "7") (pinfunction "EN_7") (pintype "bidirectional"))
    )
    (net (code "195") (name "Net-(U8-FB)") (class "Default")
      (node (ref "R48") (pin "1") (pinfunction "1_1") (pintype "passive"))
      (node (ref "R52") (pin "1") (pinfunction "1_1") (pintype "passive"))
      (node (ref "U8") (pin "5") (pinfunction "FB_5") (pintype "bidirectional"))
    )
    (net (code "196") (name "Net-(U8-SS)") (class "Default")
      (node (ref "C53") (pin "1") (pinfunction "1_1") (pintype "passive"))
      (node (ref "U8") (pin "8") (pinfunction "SS_8") (pintype "bidirectional"))
    )
    (net (code "197") (name "Net-(U8-SW)") (class "Default")
      (node (ref "C49") (pin "2") (pinfunction "2_2") (pintype "passive"))
      (node (ref "L7") (pin "1") (pinfunction "1_1") (pintype "passive"))
      (node (ref "U8") (pin "3") (pinfunction "SW_3") (pintype "bidirectional"))
    )
    (net (code "198") (name "Net-(U9-FB)") (class "Default")
      (node (ref "C51") (pin "2") (pinfunction "2_2") (pintype "passive"))
      (node (ref "R49") (pin "2") (pinfunction "2_2") (pintype "passive"))
      (node (ref "R53") (pin "1") (pinfunction "1_1") (pintype "passive"))
      (node (ref "U9") (pin "5") (pinfunction "FB_5") (pintype "bidirectional"))
    )
    (net (code "199") (name "Net-(U9-LX)") (class "Default")
      (node (ref "L6") (pin "1") (pinfunction "1_1") (pintype "passive"))
      (node (ref "U9") (pin "3") (pinfunction "LX_3") (pintype "bidirectional"))
    )
    (net (code "200") (name "Net-(WKUP-1)") (class "Default")
      (node (ref "C35") (pin "1") (pinfunction "1_1") (pintype "passive"))
      (node (ref "R30") (pin "1") (pinfunction "1_1") (pintype "passive"))
      (node (ref "R32") (pin "2") (pinfunction "2_2") (pintype "passive"))
      (node (ref "WKUP") (pin "P$2") (pinfunction "1_P$2") (pintype "passive"))
    )
    (net (code "201") (name "VIN") (class "Default")
      (node (ref "C52") (pin "+") (pinfunction "+_+") (pintype "passive"))
      (node (ref "CON1") (pin "6") (pinfunction "6_6") (pintype "passive"))
      (node (ref "D4") (pin "C") (pinfunction "C_C") (pintype "passive"))
      (node (ref "PWR_JACK") (pin "+") (pinfunction "+_+") (pintype "passive"))
      (node (ref "R47") (pin "1") (pinfunction "1_1") (pintype "passive"))
      (node (ref "U4") (pin "VIN") (pinfunction "VIN_VIN") (pintype "bidirectional"))
      (node (ref "U8") (pin "2") (pinfunction "IN_2") (pintype "bidirectional"))
    )
    (net (code "202") (name "unconnected-(U3-CRS-Pad14)") (class "Default")
      (node (ref "U3") (pin "14") (pinfunction "CRS_14") (pintype "output"))
    )
    (net (code "203") (name "unconnected-(U3-RXDV-Pad26)") (class "Default")
      (node (ref "U3") (pin "26") (pinfunction "RXDV_26") (pintype "output"))
    )
    (net (code "204") (name "unconnected-(U3-TXCLK-Pad20)") (class "Default")
      (node (ref "U3") (pin "20") (pinfunction "TXCLK_20") (pintype "output"))
    )
    (net (code "205") (name "unconnected-(U3-XTAL2-Pad4)") (class "Default")
      (node (ref "U3") (pin "4") (pinfunction "XTAL2_4") (pintype "output"))
    )
  )
)
